# SchematicEasyEDA.net
KiCad netlist of a schematic drawn in EasyEDA
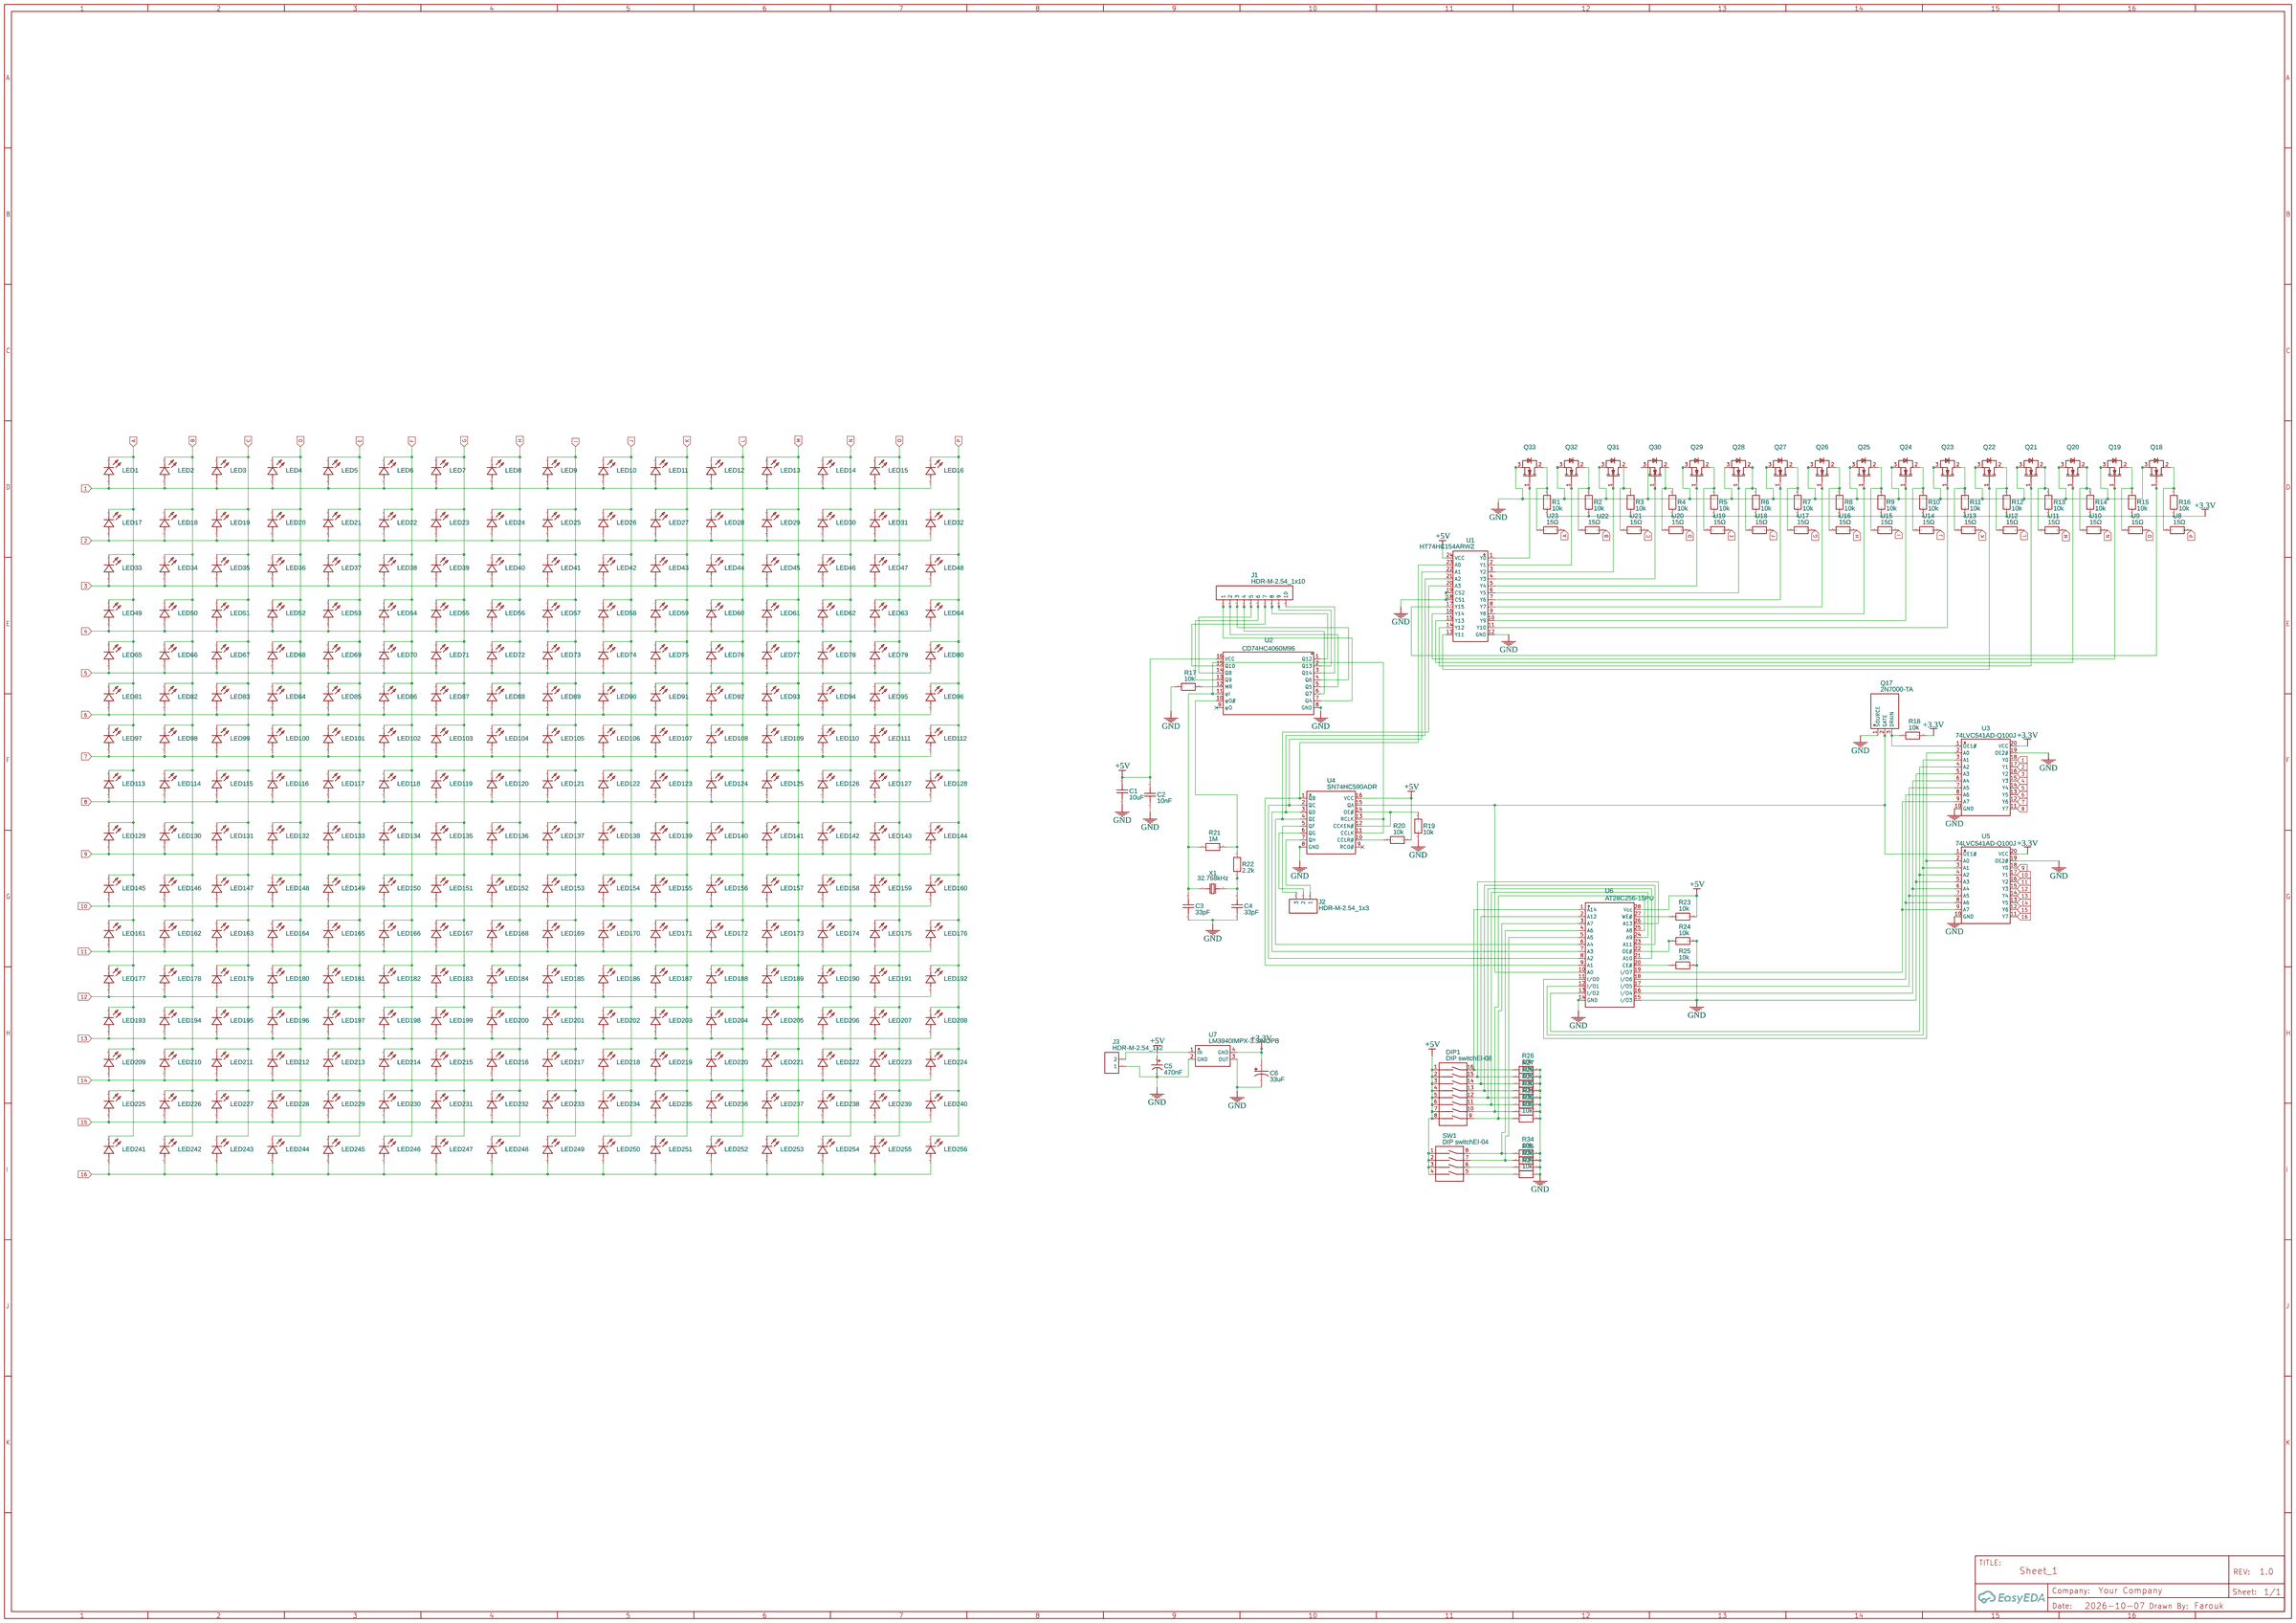
[diagram p0: schematic sheet]

(export (version "E")
  (design (tool "Eeschema 10.0.6"))
  (components
    (comp (ref "C1")
      (value "10uF")
      (fields
        (field (name "Manufacturer Part") "CC1210Y5V16V106ZN")
        (field (name "Manufacturer") "TORCH(火炬)")
      )
      (libsource (lib "") (part "CC1210Y5V16V106ZN"))
    )
    (comp (ref "C2")
      (value "10nF")
      (fields
        (field (name "Manufacturer Part") "CSA0805C0G103J500MT")
        (field (name "Manufacturer") "HRE(芯声)")
      )
      (libsource (lib "") (part "CSA0805C0G103J500MT"))
    )
    (comp (ref "C3")
      (value "33pF")
      (fields (field (name "Manufacturer Part") "600F330JT250XT") (field (name "Manufacturer") "Kyocera AVX"))
      (libsource (lib "") (part "600F330JT250XT"))
    )
    (comp (ref "C4")
      (value "33pF")
      (fields (field (name "Manufacturer Part") "600F330JT250XT") (field (name "Manufacturer") "Kyocera AVX"))
      (libsource (lib "") (part "600F330JT250XT"))
    )
    (comp (ref "C5")
      (value "470nF")
      (fields
        (field (name "Manufacturer Part") "kF474M050C05RR0VH2FP0")
        (field (name "Manufacturer") "Chengx(承兴)")
      )
      (libsource (lib "") (part "0.47uF 50V 4*5"))
    )
    (comp (ref "C6")
      (value "33uF")
      (fields
        (field (name "Manufacturer Part") "ECR1HPT330MLL063011")
        (field (name "Manufacturer") "Jianghai(南通江海)")
      )
      (libsource (lib "") (part "ECR1HPT330MLL063011"))
    )
    (comp (ref "DIP1")
      (value "DIP switchEI-08")
      (fields (field (name "Manufacturer Part") "EI-08-V") (field (name "Manufacturer") "Diptronics(圜达)"))
      (libsource (lib "") (part "DIP switchEI-08"))
    )
    (comp (ref "J1")
      (value "HDR-M-2.54_1x10")
      (fields
        (field (name "Manufacturer Part") "HX PZ-2005WV-1x10P")
        (field (name "Manufacturer") "hanxia(韩下)")
      )
      (libsource (lib "") (part "HDR-M-2.54_1x10"))
    )
    (comp (ref "J2")
      (value "HDR-M-2.54_1x3")
      (fields
        (field (name "Manufacturer Part") "5557WRF-1X3P(HDGC4201WR-F-1X3P)")
        (field (name "Manufacturer") "HDGC(华德共创)")
      )
      (libsource (lib "") (part "HDR-M-2.54_1x3"))
    )
    (comp (ref "J3") (value "HDR-M-2.54_1x2") (libsource (lib "") (part "HDR-M-2.54_1x2")))
    (comp (ref "LED1")
      (value "42-21A/GHC-YX1Y2N/1T")
      (fields (field (name "Manufacturer") "EVERLIGHT(亿光)"))
      (libsource (lib "") (part "42-21A/GHC-YX1Y2N/1T"))
    )
    (comp (ref "LED2")
      (value "42-21A/GHC-YX1Y2N/1T")
      (fields (field (name "Manufacturer") "EVERLIGHT(亿光)"))
      (libsource (lib "") (part "42-21A/GHC-YX1Y2N/1T"))
    )
    (comp (ref "LED3")
      (value "42-21A/GHC-YX1Y2N/1T")
      (fields (field (name "Manufacturer") "EVERLIGHT(亿光)"))
      (libsource (lib "") (part "42-21A/GHC-YX1Y2N/1T"))
    )
    (comp (ref "LED4")
      (value "42-21A/GHC-YX1Y2N/1T")
      (fields (field (name "Manufacturer") "EVERLIGHT(亿光)"))
      (libsource (lib "") (part "42-21A/GHC-YX1Y2N/1T"))
    )
    (comp (ref "LED5")
      (value "42-21A/GHC-YX1Y2N/1T")
      (fields (field (name "Manufacturer") "EVERLIGHT(亿光)"))
      (libsource (lib "") (part "42-21A/GHC-YX1Y2N/1T"))
    )
    (comp (ref "LED6")
      (value "42-21A/GHC-YX1Y2N/1T")
      (fields (field (name "Manufacturer") "EVERLIGHT(亿光)"))
      (libsource (lib "") (part "42-21A/GHC-YX1Y2N/1T"))
    )
    (comp (ref "LED7")
      (value "42-21A/GHC-YX1Y2N/1T")
      (fields (field (name "Manufacturer") "EVERLIGHT(亿光)"))
      (libsource (lib "") (part "42-21A/GHC-YX1Y2N/1T"))
    )
    (comp (ref "LED8")
      (value "42-21A/GHC-YX1Y2N/1T")
      (fields (field (name "Manufacturer") "EVERLIGHT(亿光)"))
      (libsource (lib "") (part "42-21A/GHC-YX1Y2N/1T"))
    )
    (comp (ref "LED9")
      (value "42-21A/GHC-YX1Y2N/1T")
      (fields (field (name "Manufacturer") "EVERLIGHT(亿光)"))
      (libsource (lib "") (part "42-21A/GHC-YX1Y2N/1T"))
    )
    (comp (ref "LED10")
      (value "42-21A/GHC-YX1Y2N/1T")
      (fields (field (name "Manufacturer") "EVERLIGHT(亿光)"))
      (libsource (lib "") (part "42-21A/GHC-YX1Y2N/1T"))
    )
    (comp (ref "LED11")
      (value "42-21A/GHC-YX1Y2N/1T")
      (fields (field (name "Manufacturer") "EVERLIGHT(亿光)"))
      (libsource (lib "") (part "42-21A/GHC-YX1Y2N/1T"))
    )
    (comp (ref "LED12")
      (value "42-21A/GHC-YX1Y2N/1T")
      (fields (field (name "Manufacturer") "EVERLIGHT(亿光)"))
      (libsource (lib "") (part "42-21A/GHC-YX1Y2N/1T"))
    )
    (comp (ref "LED13")
      (value "42-21A/GHC-YX1Y2N/1T")
      (fields (field (name "Manufacturer") "EVERLIGHT(亿光)"))
      (libsource (lib "") (part "42-21A/GHC-YX1Y2N/1T"))
    )
    (comp (ref "LED14")
      (value "42-21A/GHC-YX1Y2N/1T")
      (fields (field (name "Manufacturer") "EVERLIGHT(亿光)"))
      (libsource (lib "") (part "42-21A/GHC-YX1Y2N/1T"))
    )
    (comp (ref "LED15")
      (value "42-21A/GHC-YX1Y2N/1T")
      (fields (field (name "Manufacturer") "EVERLIGHT(亿光)"))
      (libsource (lib "") (part "42-21A/GHC-YX1Y2N/1T"))
    )
    (comp (ref "LED16")
      (value "42-21A/GHC-YX1Y2N/1T")
      (fields (field (name "Manufacturer") "EVERLIGHT(亿光)"))
      (libsource (lib "") (part "42-21A/GHC-YX1Y2N/1T"))
    )
    (comp (ref "LED17")
      (value "42-21A/GHC-YX1Y2N/1T")
      (fields (field (name "Manufacturer") "EVERLIGHT(亿光)"))
      (libsource (lib "") (part "42-21A/GHC-YX1Y2N/1T"))
    )
    (comp (ref "LED18")
      (value "42-21A/GHC-YX1Y2N/1T")
      (fields (field (name "Manufacturer") "EVERLIGHT(亿光)"))
      (libsource (lib "") (part "42-21A/GHC-YX1Y2N/1T"))
    )
    (comp (ref "LED19")
      (value "42-21A/GHC-YX1Y2N/1T")
      (fields (field (name "Manufacturer") "EVERLIGHT(亿光)"))
      (libsource (lib "") (part "42-21A/GHC-YX1Y2N/1T"))
    )
    (comp (ref "LED20")
      (value "42-21A/GHC-YX1Y2N/1T")
      (fields (field (name "Manufacturer") "EVERLIGHT(亿光)"))
      (libsource (lib "") (part "42-21A/GHC-YX1Y2N/1T"))
    )
    (comp (ref "LED21")
      (value "42-21A/GHC-YX1Y2N/1T")
      (fields (field (name "Manufacturer") "EVERLIGHT(亿光)"))
      (libsource (lib "") (part "42-21A/GHC-YX1Y2N/1T"))
    )
    (comp (ref "LED22")
      (value "42-21A/GHC-YX1Y2N/1T")
      (fields (field (name "Manufacturer") "EVERLIGHT(亿光)"))
      (libsource (lib "") (part "42-21A/GHC-YX1Y2N/1T"))
    )
    (comp (ref "LED23")
      (value "42-21A/GHC-YX1Y2N/1T")
      (fields (field (name "Manufacturer") "EVERLIGHT(亿光)"))
      (libsource (lib "") (part "42-21A/GHC-YX1Y2N/1T"))
    )
    (comp (ref "LED24")
      (value "42-21A/GHC-YX1Y2N/1T")
      (fields (field (name "Manufacturer") "EVERLIGHT(亿光)"))
      (libsource (lib "") (part "42-21A/GHC-YX1Y2N/1T"))
    )
    (comp (ref "LED25")
      (value "42-21A/GHC-YX1Y2N/1T")
      (fields (field (name "Manufacturer") "EVERLIGHT(亿光)"))
      (libsource (lib "") (part "42-21A/GHC-YX1Y2N/1T"))
    )
    (comp (ref "LED26")
      (value "42-21A/GHC-YX1Y2N/1T")
      (fields (field (name "Manufacturer") "EVERLIGHT(亿光)"))
      (libsource (lib "") (part "42-21A/GHC-YX1Y2N/1T"))
    )
    (comp (ref "LED27")
      (value "42-21A/GHC-YX1Y2N/1T")
      (fields (field (name "Manufacturer") "EVERLIGHT(亿光)"))
      (libsource (lib "") (part "42-21A/GHC-YX1Y2N/1T"))
    )
    (comp (ref "LED28")
      (value "42-21A/GHC-YX1Y2N/1T")
      (fields (field (name "Manufacturer") "EVERLIGHT(亿光)"))
      (libsource (lib "") (part "42-21A/GHC-YX1Y2N/1T"))
    )
    (comp (ref "LED29")
      (value "42-21A/GHC-YX1Y2N/1T")
      (fields (field (name "Manufacturer") "EVERLIGHT(亿光)"))
      (libsource (lib "") (part "42-21A/GHC-YX1Y2N/1T"))
    )
    (comp (ref "LED30")
      (value "42-21A/GHC-YX1Y2N/1T")
      (fields (field (name "Manufacturer") "EVERLIGHT(亿光)"))
      (libsource (lib "") (part "42-21A/GHC-YX1Y2N/1T"))
    )
    (comp (ref "LED31")
      (value "42-21A/GHC-YX1Y2N/1T")
      (fields (field (name "Manufacturer") "EVERLIGHT(亿光)"))
      (libsource (lib "") (part "42-21A/GHC-YX1Y2N/1T"))
    )
    (comp (ref "LED32")
      (value "42-21A/GHC-YX1Y2N/1T")
      (fields (field (name "Manufacturer") "EVERLIGHT(亿光)"))
      (libsource (lib "") (part "42-21A/GHC-YX1Y2N/1T"))
    )
    (comp (ref "LED33")
      (value "42-21A/GHC-YX1Y2N/1T")
      (fields (field (name "Manufacturer") "EVERLIGHT(亿光)"))
      (libsource (lib "") (part "42-21A/GHC-YX1Y2N/1T"))
    )
    (comp (ref "LED34")
      (value "42-21A/GHC-YX1Y2N/1T")
      (fields (field (name "Manufacturer") "EVERLIGHT(亿光)"))
      (libsource (lib "") (part "42-21A/GHC-YX1Y2N/1T"))
    )
    (comp (ref "LED35")
      (value "42-21A/GHC-YX1Y2N/1T")
      (fields (field (name "Manufacturer") "EVERLIGHT(亿光)"))
      (libsource (lib "") (part "42-21A/GHC-YX1Y2N/1T"))
    )
    (comp (ref "LED36")
      (value "42-21A/GHC-YX1Y2N/1T")
      (fields (field (name "Manufacturer") "EVERLIGHT(亿光)"))
      (libsource (lib "") (part "42-21A/GHC-YX1Y2N/1T"))
    )
    (comp (ref "LED37")
      (value "42-21A/GHC-YX1Y2N/1T")
      (fields (field (name "Manufacturer") "EVERLIGHT(亿光)"))
      (libsource (lib "") (part "42-21A/GHC-YX1Y2N/1T"))
    )
    (comp (ref "LED38")
      (value "42-21A/GHC-YX1Y2N/1T")
      (fields (field (name "Manufacturer") "EVERLIGHT(亿光)"))
      (libsource (lib "") (part "42-21A/GHC-YX1Y2N/1T"))
    )
    (comp (ref "LED39")
      (value "42-21A/GHC-YX1Y2N/1T")
      (fields (field (name "Manufacturer") "EVERLIGHT(亿光)"))
      (libsource (lib "") (part "42-21A/GHC-YX1Y2N/1T"))
    )
    (comp (ref "LED40")
      (value "42-21A/GHC-YX1Y2N/1T")
      (fields (field (name "Manufacturer") "EVERLIGHT(亿光)"))
      (libsource (lib "") (part "42-21A/GHC-YX1Y2N/1T"))
    )
    (comp (ref "LED41")
      (value "42-21A/GHC-YX1Y2N/1T")
      (fields (field (name "Manufacturer") "EVERLIGHT(亿光)"))
      (libsource (lib "") (part "42-21A/GHC-YX1Y2N/1T"))
    )
    (comp (ref "LED42")
      (value "42-21A/GHC-YX1Y2N/1T")
      (fields (field (name "Manufacturer") "EVERLIGHT(亿光)"))
      (libsource (lib "") (part "42-21A/GHC-YX1Y2N/1T"))
    )
    (comp (ref "LED43")
      (value "42-21A/GHC-YX1Y2N/1T")
      (fields (field (name "Manufacturer") "EVERLIGHT(亿光)"))
      (libsource (lib "") (part "42-21A/GHC-YX1Y2N/1T"))
    )
    (comp (ref "LED44")
      (value "42-21A/GHC-YX1Y2N/1T")
      (fields (field (name "Manufacturer") "EVERLIGHT(亿光)"))
      (libsource (lib "") (part "42-21A/GHC-YX1Y2N/1T"))
    )
    (comp (ref "LED45")
      (value "42-21A/GHC-YX1Y2N/1T")
      (fields (field (name "Manufacturer") "EVERLIGHT(亿光)"))
      (libsource (lib "") (part "42-21A/GHC-YX1Y2N/1T"))
    )
    (comp (ref "LED46")
      (value "42-21A/GHC-YX1Y2N/1T")
      (fields (field (name "Manufacturer") "EVERLIGHT(亿光)"))
      (libsource (lib "") (part "42-21A/GHC-YX1Y2N/1T"))
    )
    (comp (ref "LED47")
      (value "42-21A/GHC-YX1Y2N/1T")
      (fields (field (name "Manufacturer") "EVERLIGHT(亿光)"))
      (libsource (lib "") (part "42-21A/GHC-YX1Y2N/1T"))
    )
    (comp (ref "LED48")
      (value "42-21A/GHC-YX1Y2N/1T")
      (fields (field (name "Manufacturer") "EVERLIGHT(亿光)"))
      (libsource (lib "") (part "42-21A/GHC-YX1Y2N/1T"))
    )
    (comp (ref "LED49")
      (value "42-21A/GHC-YX1Y2N/1T")
      (fields (field (name "Manufacturer") "EVERLIGHT(亿光)"))
      (libsource (lib "") (part "42-21A/GHC-YX1Y2N/1T"))
    )
    (comp (ref "LED50")
      (value "42-21A/GHC-YX1Y2N/1T")
      (fields (field (name "Manufacturer") "EVERLIGHT(亿光)"))
      (libsource (lib "") (part "42-21A/GHC-YX1Y2N/1T"))
    )
    (comp (ref "LED51")
      (value "42-21A/GHC-YX1Y2N/1T")
      (fields (field (name "Manufacturer") "EVERLIGHT(亿光)"))
      (libsource (lib "") (part "42-21A/GHC-YX1Y2N/1T"))
    )
    (comp (ref "LED52")
      (value "42-21A/GHC-YX1Y2N/1T")
      (fields (field (name "Manufacturer") "EVERLIGHT(亿光)"))
      (libsource (lib "") (part "42-21A/GHC-YX1Y2N/1T"))
    )
    (comp (ref "LED53")
      (value "42-21A/GHC-YX1Y2N/1T")
      (fields (field (name "Manufacturer") "EVERLIGHT(亿光)"))
      (libsource (lib "") (part "42-21A/GHC-YX1Y2N/1T"))
    )
    (comp (ref "LED54")
      (value "42-21A/GHC-YX1Y2N/1T")
      (fields (field (name "Manufacturer") "EVERLIGHT(亿光)"))
      (libsource (lib "") (part "42-21A/GHC-YX1Y2N/1T"))
    )
    (comp (ref "LED55")
      (value "42-21A/GHC-YX1Y2N/1T")
      (fields (field (name "Manufacturer") "EVERLIGHT(亿光)"))
      (libsource (lib "") (part "42-21A/GHC-YX1Y2N/1T"))
    )
    (comp (ref "LED56")
      (value "42-21A/GHC-YX1Y2N/1T")
      (fields (field (name "Manufacturer") "EVERLIGHT(亿光)"))
      (libsource (lib "") (part "42-21A/GHC-YX1Y2N/1T"))
    )
    (comp (ref "LED57")
      (value "42-21A/GHC-YX1Y2N/1T")
      (fields (field (name "Manufacturer") "EVERLIGHT(亿光)"))
      (libsource (lib "") (part "42-21A/GHC-YX1Y2N/1T"))
    )
    (comp (ref "LED58")
      (value "42-21A/GHC-YX1Y2N/1T")
      (fields (field (name "Manufacturer") "EVERLIGHT(亿光)"))
      (libsource (lib "") (part "42-21A/GHC-YX1Y2N/1T"))
    )
    (comp (ref "LED59")
      (value "42-21A/GHC-YX1Y2N/1T")
      (fields (field (name "Manufacturer") "EVERLIGHT(亿光)"))
      (libsource (lib "") (part "42-21A/GHC-YX1Y2N/1T"))
    )
    (comp (ref "LED60")
      (value "42-21A/GHC-YX1Y2N/1T")
      (fields (field (name "Manufacturer") "EVERLIGHT(亿光)"))
      (libsource (lib "") (part "42-21A/GHC-YX1Y2N/1T"))
    )
    (comp (ref "LED61")
      (value "42-21A/GHC-YX1Y2N/1T")
      (fields (field (name "Manufacturer") "EVERLIGHT(亿光)"))
      (libsource (lib "") (part "42-21A/GHC-YX1Y2N/1T"))
    )
    (comp (ref "LED62")
      (value "42-21A/GHC-YX1Y2N/1T")
      (fields (field (name "Manufacturer") "EVERLIGHT(亿光)"))
      (libsource (lib "") (part "42-21A/GHC-YX1Y2N/1T"))
    )
    (comp (ref "LED63")
      (value "42-21A/GHC-YX1Y2N/1T")
      (fields (field (name "Manufacturer") "EVERLIGHT(亿光)"))
      (libsource (lib "") (part "42-21A/GHC-YX1Y2N/1T"))
    )
    (comp (ref "LED64")
      (value "42-21A/GHC-YX1Y2N/1T")
      (fields (field (name "Manufacturer") "EVERLIGHT(亿光)"))
      (libsource (lib "") (part "42-21A/GHC-YX1Y2N/1T"))
    )
    (comp (ref "LED65")
      (value "42-21A/GHC-YX1Y2N/1T")
      (fields (field (name "Manufacturer") "EVERLIGHT(亿光)"))
      (libsource (lib "") (part "42-21A/GHC-YX1Y2N/1T"))
    )
    (comp (ref "LED66")
      (value "42-21A/GHC-YX1Y2N/1T")
      (fields (field (name "Manufacturer") "EVERLIGHT(亿光)"))
      (libsource (lib "") (part "42-21A/GHC-YX1Y2N/1T"))
    )
    (comp (ref "LED67")
      (value "42-21A/GHC-YX1Y2N/1T")
      (fields (field (name "Manufacturer") "EVERLIGHT(亿光)"))
      (libsource (lib "") (part "42-21A/GHC-YX1Y2N/1T"))
    )
    (comp (ref "LED68")
      (value "42-21A/GHC-YX1Y2N/1T")
      (fields (field (name "Manufacturer") "EVERLIGHT(亿光)"))
      (libsource (lib "") (part "42-21A/GHC-YX1Y2N/1T"))
    )
    (comp (ref "LED69")
      (value "42-21A/GHC-YX1Y2N/1T")
      (fields (field (name "Manufacturer") "EVERLIGHT(亿光)"))
      (libsource (lib "") (part "42-21A/GHC-YX1Y2N/1T"))
    )
    (comp (ref "LED70")
      (value "42-21A/GHC-YX1Y2N/1T")
      (fields (field (name "Manufacturer") "EVERLIGHT(亿光)"))
      (libsource (lib "") (part "42-21A/GHC-YX1Y2N/1T"))
    )
    (comp (ref "LED71")
      (value "42-21A/GHC-YX1Y2N/1T")
      (fields (field (name "Manufacturer") "EVERLIGHT(亿光)"))
      (libsource (lib "") (part "42-21A/GHC-YX1Y2N/1T"))
    )
    (comp (ref "LED72")
      (value "42-21A/GHC-YX1Y2N/1T")
      (fields (field (name "Manufacturer") "EVERLIGHT(亿光)"))
      (libsource (lib "") (part "42-21A/GHC-YX1Y2N/1T"))
    )
    (comp (ref "LED73")
      (value "42-21A/GHC-YX1Y2N/1T")
      (fields (field (name "Manufacturer") "EVERLIGHT(亿光)"))
      (libsource (lib "") (part "42-21A/GHC-YX1Y2N/1T"))
    )
    (comp (ref "LED74")
      (value "42-21A/GHC-YX1Y2N/1T")
      (fields (field (name "Manufacturer") "EVERLIGHT(亿光)"))
      (libsource (lib "") (part "42-21A/GHC-YX1Y2N/1T"))
    )
    (comp (ref "LED75")
      (value "42-21A/GHC-YX1Y2N/1T")
      (fields (field (name "Manufacturer") "EVERLIGHT(亿光)"))
      (libsource (lib "") (part "42-21A/GHC-YX1Y2N/1T"))
    )
    (comp (ref "LED76")
      (value "42-21A/GHC-YX1Y2N/1T")
      (fields (field (name "Manufacturer") "EVERLIGHT(亿光)"))
      (libsource (lib "") (part "42-21A/GHC-YX1Y2N/1T"))
    )
    (comp (ref "LED77")
      (value "42-21A/GHC-YX1Y2N/1T")
      (fields (field (name "Manufacturer") "EVERLIGHT(亿光)"))
      (libsource (lib "") (part "42-21A/GHC-YX1Y2N/1T"))
    )
    (comp (ref "LED78")
      (value "42-21A/GHC-YX1Y2N/1T")
      (fields (field (name "Manufacturer") "EVERLIGHT(亿光)"))
      (libsource (lib "") (part "42-21A/GHC-YX1Y2N/1T"))
    )
    (comp (ref "LED79")
      (value "42-21A/GHC-YX1Y2N/1T")
      (fields (field (name "Manufacturer") "EVERLIGHT(亿光)"))
      (libsource (lib "") (part "42-21A/GHC-YX1Y2N/1T"))
    )
    (comp (ref "LED80")
      (value "42-21A/GHC-YX1Y2N/1T")
      (fields (field (name "Manufacturer") "EVERLIGHT(亿光)"))
      (libsource (lib "") (part "42-21A/GHC-YX1Y2N/1T"))
    )
    (comp (ref "LED81")
      (value "42-21A/GHC-YX1Y2N/1T")
      (fields (field (name "Manufacturer") "EVERLIGHT(亿光)"))
      (libsource (lib "") (part "42-21A/GHC-YX1Y2N/1T"))
    )
    (comp (ref "LED82")
      (value "42-21A/GHC-YX1Y2N/1T")
      (fields (field (name "Manufacturer") "EVERLIGHT(亿光)"))
      (libsource (lib "") (part "42-21A/GHC-YX1Y2N/1T"))
    )
    (comp (ref "LED83")
      (value "42-21A/GHC-YX1Y2N/1T")
      (fields (field (name "Manufacturer") "EVERLIGHT(亿光)"))
      (libsource (lib "") (part "42-21A/GHC-YX1Y2N/1T"))
    )
    (comp (ref "LED84")
      (value "42-21A/GHC-YX1Y2N/1T")
      (fields (field (name "Manufacturer") "EVERLIGHT(亿光)"))
      (libsource (lib "") (part "42-21A/GHC-YX1Y2N/1T"))
    )
    (comp (ref "LED85")
      (value "42-21A/GHC-YX1Y2N/1T")
      (fields (field (name "Manufacturer") "EVERLIGHT(亿光)"))
      (libsource (lib "") (part "42-21A/GHC-YX1Y2N/1T"))
    )
    (comp (ref "LED86")
      (value "42-21A/GHC-YX1Y2N/1T")
      (fields (field (name "Manufacturer") "EVERLIGHT(亿光)"))
      (libsource (lib "") (part "42-21A/GHC-YX1Y2N/1T"))
    )
    (comp (ref "LED87")
      (value "42-21A/GHC-YX1Y2N/1T")
      (fields (field (name "Manufacturer") "EVERLIGHT(亿光)"))
      (libsource (lib "") (part "42-21A/GHC-YX1Y2N/1T"))
    )
    (comp (ref "LED88")
      (value "42-21A/GHC-YX1Y2N/1T")
      (fields (field (name "Manufacturer") "EVERLIGHT(亿光)"))
      (libsource (lib "") (part "42-21A/GHC-YX1Y2N/1T"))
    )
    (comp (ref "LED89")
      (value "42-21A/GHC-YX1Y2N/1T")
      (fields (field (name "Manufacturer") "EVERLIGHT(亿光)"))
      (libsource (lib "") (part "42-21A/GHC-YX1Y2N/1T"))
    )
    (comp (ref "LED90")
      (value "42-21A/GHC-YX1Y2N/1T")
      (fields (field (name "Manufacturer") "EVERLIGHT(亿光)"))
      (libsource (lib "") (part "42-21A/GHC-YX1Y2N/1T"))
    )
    (comp (ref "LED91")
      (value "42-21A/GHC-YX1Y2N/1T")
      (fields (field (name "Manufacturer") "EVERLIGHT(亿光)"))
      (libsource (lib "") (part "42-21A/GHC-YX1Y2N/1T"))
    )
    (comp (ref "LED92")
      (value "42-21A/GHC-YX1Y2N/1T")
      (fields (field (name "Manufacturer") "EVERLIGHT(亿光)"))
      (libsource (lib "") (part "42-21A/GHC-YX1Y2N/1T"))
    )
    (comp (ref "LED93")
      (value "42-21A/GHC-YX1Y2N/1T")
      (fields (field (name "Manufacturer") "EVERLIGHT(亿光)"))
      (libsource (lib "") (part "42-21A/GHC-YX1Y2N/1T"))
    )
    (comp (ref "LED94")
      (value "42-21A/GHC-YX1Y2N/1T")
      (fields (field (name "Manufacturer") "EVERLIGHT(亿光)"))
      (libsource (lib "") (part "42-21A/GHC-YX1Y2N/1T"))
    )
    (comp (ref "LED95")
      (value "42-21A/GHC-YX1Y2N/1T")
      (fields (field (name "Manufacturer") "EVERLIGHT(亿光)"))
      (libsource (lib "") (part "42-21A/GHC-YX1Y2N/1T"))
    )
    (comp (ref "LED96")
      (value "42-21A/GHC-YX1Y2N/1T")
      (fields (field (name "Manufacturer") "EVERLIGHT(亿光)"))
      (libsource (lib "") (part "42-21A/GHC-YX1Y2N/1T"))
    )
    (comp (ref "LED97")
      (value "42-21A/GHC-YX1Y2N/1T")
      (fields (field (name "Manufacturer") "EVERLIGHT(亿光)"))
      (libsource (lib "") (part "42-21A/GHC-YX1Y2N/1T"))
    )
    (comp (ref "LED98")
      (value "42-21A/GHC-YX1Y2N/1T")
      (fields (field (name "Manufacturer") "EVERLIGHT(亿光)"))
      (libsource (lib "") (part "42-21A/GHC-YX1Y2N/1T"))
    )
    (comp (ref "LED99")
      (value "42-21A/GHC-YX1Y2N/1T")
      (fields (field (name "Manufacturer") "EVERLIGHT(亿光)"))
      (libsource (lib "") (part "42-21A/GHC-YX1Y2N/1T"))
    )
    (comp (ref "LED100")
      (value "42-21A/GHC-YX1Y2N/1T")
      (fields (field (name "Manufacturer") "EVERLIGHT(亿光)"))
      (libsource (lib "") (part "42-21A/GHC-YX1Y2N/1T"))
    )
    (comp (ref "LED101")
      (value "42-21A/GHC-YX1Y2N/1T")
      (fields (field (name "Manufacturer") "EVERLIGHT(亿光)"))
      (libsource (lib "") (part "42-21A/GHC-YX1Y2N/1T"))
    )
    (comp (ref "LED102")
      (value "42-21A/GHC-YX1Y2N/1T")
      (fields (field (name "Manufacturer") "EVERLIGHT(亿光)"))
      (libsource (lib "") (part "42-21A/GHC-YX1Y2N/1T"))
    )
    (comp (ref "LED103")
      (value "42-21A/GHC-YX1Y2N/1T")
      (fields (field (name "Manufacturer") "EVERLIGHT(亿光)"))
      (libsource (lib "") (part "42-21A/GHC-YX1Y2N/1T"))
    )
    (comp (ref "LED104")
      (value "42-21A/GHC-YX1Y2N/1T")
      (fields (field (name "Manufacturer") "EVERLIGHT(亿光)"))
      (libsource (lib "") (part "42-21A/GHC-YX1Y2N/1T"))
    )
    (comp (ref "LED105")
      (value "42-21A/GHC-YX1Y2N/1T")
      (fields (field (name "Manufacturer") "EVERLIGHT(亿光)"))
      (libsource (lib "") (part "42-21A/GHC-YX1Y2N/1T"))
    )
    (comp (ref "LED106")
      (value "42-21A/GHC-YX1Y2N/1T")
      (fields (field (name "Manufacturer") "EVERLIGHT(亿光)"))
      (libsource (lib "") (part "42-21A/GHC-YX1Y2N/1T"))
    )
    (comp (ref "LED107")
      (value "42-21A/GHC-YX1Y2N/1T")
      (fields (field (name "Manufacturer") "EVERLIGHT(亿光)"))
      (libsource (lib "") (part "42-21A/GHC-YX1Y2N/1T"))
    )
    (comp (ref "LED108")
      (value "42-21A/GHC-YX1Y2N/1T")
      (fields (field (name "Manufacturer") "EVERLIGHT(亿光)"))
      (libsource (lib "") (part "42-21A/GHC-YX1Y2N/1T"))
    )
    (comp (ref "LED109")
      (value "42-21A/GHC-YX1Y2N/1T")
      (fields (field (name "Manufacturer") "EVERLIGHT(亿光)"))
      (libsource (lib "") (part "42-21A/GHC-YX1Y2N/1T"))
    )
    (comp (ref "LED110")
      (value "42-21A/GHC-YX1Y2N/1T")
      (fields (field (name "Manufacturer") "EVERLIGHT(亿光)"))
      (libsource (lib "") (part "42-21A/GHC-YX1Y2N/1T"))
    )
    (comp (ref "LED111")
      (value "42-21A/GHC-YX1Y2N/1T")
      (fields (field (name "Manufacturer") "EVERLIGHT(亿光)"))
      (libsource (lib "") (part "42-21A/GHC-YX1Y2N/1T"))
    )
    (comp (ref "LED112")
      (value "42-21A/GHC-YX1Y2N/1T")
      (fields (field (name "Manufacturer") "EVERLIGHT(亿光)"))
      (libsource (lib "") (part "42-21A/GHC-YX1Y2N/1T"))
    )
    (comp (ref "LED113")
      (value "42-21A/GHC-YX1Y2N/1T")
      (fields (field (name "Manufacturer") "EVERLIGHT(亿光)"))
      (libsource (lib "") (part "42-21A/GHC-YX1Y2N/1T"))
    )
    (comp (ref "LED114")
      (value "42-21A/GHC-YX1Y2N/1T")
      (fields (field (name "Manufacturer") "EVERLIGHT(亿光)"))
      (libsource (lib "") (part "42-21A/GHC-YX1Y2N/1T"))
    )
    (comp (ref "LED115")
      (value "42-21A/GHC-YX1Y2N/1T")
      (fields (field (name "Manufacturer") "EVERLIGHT(亿光)"))
      (libsource (lib "") (part "42-21A/GHC-YX1Y2N/1T"))
    )
    (comp (ref "LED116")
      (value "42-21A/GHC-YX1Y2N/1T")
      (fields (field (name "Manufacturer") "EVERLIGHT(亿光)"))
      (libsource (lib "") (part "42-21A/GHC-YX1Y2N/1T"))
    )
    (comp (ref "LED117")
      (value "42-21A/GHC-YX1Y2N/1T")
      (fields (field (name "Manufacturer") "EVERLIGHT(亿光)"))
      (libsource (lib "") (part "42-21A/GHC-YX1Y2N/1T"))
    )
    (comp (ref "LED118")
      (value "42-21A/GHC-YX1Y2N/1T")
      (fields (field (name "Manufacturer") "EVERLIGHT(亿光)"))
      (libsource (lib "") (part "42-21A/GHC-YX1Y2N/1T"))
    )
    (comp (ref "LED119")
      (value "42-21A/GHC-YX1Y2N/1T")
      (fields (field (name "Manufacturer") "EVERLIGHT(亿光)"))
      (libsource (lib "") (part "42-21A/GHC-YX1Y2N/1T"))
    )
    (comp (ref "LED120")
      (value "42-21A/GHC-YX1Y2N/1T")
      (fields (field (name "Manufacturer") "EVERLIGHT(亿光)"))
      (libsource (lib "") (part "42-21A/GHC-YX1Y2N/1T"))
    )
    (comp (ref "LED121")
      (value "42-21A/GHC-YX1Y2N/1T")
      (fields (field (name "Manufacturer") "EVERLIGHT(亿光)"))
      (libsource (lib "") (part "42-21A/GHC-YX1Y2N/1T"))
    )
    (comp (ref "LED122")
      (value "42-21A/GHC-YX1Y2N/1T")
      (fields (field (name "Manufacturer") "EVERLIGHT(亿光)"))
      (libsource (lib "") (part "42-21A/GHC-YX1Y2N/1T"))
    )
    (comp (ref "LED123")
      (value "42-21A/GHC-YX1Y2N/1T")
      (fields (field (name "Manufacturer") "EVERLIGHT(亿光)"))
      (libsource (lib "") (part "42-21A/GHC-YX1Y2N/1T"))
    )
    (comp (ref "LED124")
      (value "42-21A/GHC-YX1Y2N/1T")
      (fields (field (name "Manufacturer") "EVERLIGHT(亿光)"))
      (libsource (lib "") (part "42-21A/GHC-YX1Y2N/1T"))
    )
    (comp (ref "LED125")
      (value "42-21A/GHC-YX1Y2N/1T")
      (fields (field (name "Manufacturer") "EVERLIGHT(亿光)"))
      (libsource (lib "") (part "42-21A/GHC-YX1Y2N/1T"))
    )
    (comp (ref "LED126")
      (value "42-21A/GHC-YX1Y2N/1T")
      (fields (field (name "Manufacturer") "EVERLIGHT(亿光)"))
      (libsource (lib "") (part "42-21A/GHC-YX1Y2N/1T"))
    )
    (comp (ref "LED127")
      (value "42-21A/GHC-YX1Y2N/1T")
      (fields (field (name "Manufacturer") "EVERLIGHT(亿光)"))
      (libsource (lib "") (part "42-21A/GHC-YX1Y2N/1T"))
    )
    (comp (ref "LED128")
      (value "42-21A/GHC-YX1Y2N/1T")
      (fields (field (name "Manufacturer") "EVERLIGHT(亿光)"))
      (libsource (lib "") (part "42-21A/GHC-YX1Y2N/1T"))
    )
    (comp (ref "LED129")
      (value "42-21A/GHC-YX1Y2N/1T")
      (fields (field (name "Manufacturer") "EVERLIGHT(亿光)"))
      (libsource (lib "") (part "42-21A/GHC-YX1Y2N/1T"))
    )
    (comp (ref "LED130")
      (value "42-21A/GHC-YX1Y2N/1T")
      (fields (field (name "Manufacturer") "EVERLIGHT(亿光)"))
      (libsource (lib "") (part "42-21A/GHC-YX1Y2N/1T"))
    )
    (comp (ref "LED131")
      (value "42-21A/GHC-YX1Y2N/1T")
      (fields (field (name "Manufacturer") "EVERLIGHT(亿光)"))
      (libsource (lib "") (part "42-21A/GHC-YX1Y2N/1T"))
    )
    (comp (ref "LED132")
      (value "42-21A/GHC-YX1Y2N/1T")
      (fields (field (name "Manufacturer") "EVERLIGHT(亿光)"))
      (libsource (lib "") (part "42-21A/GHC-YX1Y2N/1T"))
    )
    (comp (ref "LED133")
      (value "42-21A/GHC-YX1Y2N/1T")
      (fields (field (name "Manufacturer") "EVERLIGHT(亿光)"))
      (libsource (lib "") (part "42-21A/GHC-YX1Y2N/1T"))
    )
    (comp (ref "LED134")
      (value "42-21A/GHC-YX1Y2N/1T")
      (fields (field (name "Manufacturer") "EVERLIGHT(亿光)"))
      (libsource (lib "") (part "42-21A/GHC-YX1Y2N/1T"))
    )
    (comp (ref "LED135")
      (value "42-21A/GHC-YX1Y2N/1T")
      (fields (field (name "Manufacturer") "EVERLIGHT(亿光)"))
      (libsource (lib "") (part "42-21A/GHC-YX1Y2N/1T"))
    )
    (comp (ref "LED136")
      (value "42-21A/GHC-YX1Y2N/1T")
      (fields (field (name "Manufacturer") "EVERLIGHT(亿光)"))
      (libsource (lib "") (part "42-21A/GHC-YX1Y2N/1T"))
    )
    (comp (ref "LED137")
      (value "42-21A/GHC-YX1Y2N/1T")
      (fields (field (name "Manufacturer") "EVERLIGHT(亿光)"))
      (libsource (lib "") (part "42-21A/GHC-YX1Y2N/1T"))
    )
    (comp (ref "LED138")
      (value "42-21A/GHC-YX1Y2N/1T")
      (fields (field (name "Manufacturer") "EVERLIGHT(亿光)"))
      (libsource (lib "") (part "42-21A/GHC-YX1Y2N/1T"))
    )
    (comp (ref "LED139")
      (value "42-21A/GHC-YX1Y2N/1T")
      (fields (field (name "Manufacturer") "EVERLIGHT(亿光)"))
      (libsource (lib "") (part "42-21A/GHC-YX1Y2N/1T"))
    )
    (comp (ref "LED140")
      (value "42-21A/GHC-YX1Y2N/1T")
      (fields (field (name "Manufacturer") "EVERLIGHT(亿光)"))
      (libsource (lib "") (part "42-21A/GHC-YX1Y2N/1T"))
    )
    (comp (ref "LED141")
      (value "42-21A/GHC-YX1Y2N/1T")
      (fields (field (name "Manufacturer") "EVERLIGHT(亿光)"))
      (libsource (lib "") (part "42-21A/GHC-YX1Y2N/1T"))
    )
    (comp (ref "LED142")
      (value "42-21A/GHC-YX1Y2N/1T")
      (fields (field (name "Manufacturer") "EVERLIGHT(亿光)"))
      (libsource (lib "") (part "42-21A/GHC-YX1Y2N/1T"))
    )
    (comp (ref "LED143")
      (value "42-21A/GHC-YX1Y2N/1T")
      (fields (field (name "Manufacturer") "EVERLIGHT(亿光)"))
      (libsource (lib "") (part "42-21A/GHC-YX1Y2N/1T"))
    )
    (comp (ref "LED144")
      (value "42-21A/GHC-YX1Y2N/1T")
      (fields (field (name "Manufacturer") "EVERLIGHT(亿光)"))
      (libsource (lib "") (part "42-21A/GHC-YX1Y2N/1T"))
    )
    (comp (ref "LED145")
      (value "42-21A/GHC-YX1Y2N/1T")
      (fields (field (name "Manufacturer") "EVERLIGHT(亿光)"))
      (libsource (lib "") (part "42-21A/GHC-YX1Y2N/1T"))
    )
    (comp (ref "LED146")
      (value "42-21A/GHC-YX1Y2N/1T")
      (fields (field (name "Manufacturer") "EVERLIGHT(亿光)"))
      (libsource (lib "") (part "42-21A/GHC-YX1Y2N/1T"))
    )
    (comp (ref "LED147")
      (value "42-21A/GHC-YX1Y2N/1T")
      (fields (field (name "Manufacturer") "EVERLIGHT(亿光)"))
      (libsource (lib "") (part "42-21A/GHC-YX1Y2N/1T"))
    )
    (comp (ref "LED148")
      (value "42-21A/GHC-YX1Y2N/1T")
      (fields (field (name "Manufacturer") "EVERLIGHT(亿光)"))
      (libsource (lib "") (part "42-21A/GHC-YX1Y2N/1T"))
    )
    (comp (ref "LED149")
      (value "42-21A/GHC-YX1Y2N/1T")
      (fields (field (name "Manufacturer") "EVERLIGHT(亿光)"))
      (libsource (lib "") (part "42-21A/GHC-YX1Y2N/1T"))
    )
    (comp (ref "LED150")
      (value "42-21A/GHC-YX1Y2N/1T")
      (fields (field (name "Manufacturer") "EVERLIGHT(亿光)"))
      (libsource (lib "") (part "42-21A/GHC-YX1Y2N/1T"))
    )
    (comp (ref "LED151")
      (value "42-21A/GHC-YX1Y2N/1T")
      (fields (field (name "Manufacturer") "EVERLIGHT(亿光)"))
      (libsource (lib "") (part "42-21A/GHC-YX1Y2N/1T"))
    )
    (comp (ref "LED152")
      (value "42-21A/GHC-YX1Y2N/1T")
      (fields (field (name "Manufacturer") "EVERLIGHT(亿光)"))
      (libsource (lib "") (part "42-21A/GHC-YX1Y2N/1T"))
    )
    (comp (ref "LED153")
      (value "42-21A/GHC-YX1Y2N/1T")
      (fields (field (name "Manufacturer") "EVERLIGHT(亿光)"))
      (libsource (lib "") (part "42-21A/GHC-YX1Y2N/1T"))
    )
    (comp (ref "LED154")
      (value "42-21A/GHC-YX1Y2N/1T")
      (fields (field (name "Manufacturer") "EVERLIGHT(亿光)"))
      (libsource (lib "") (part "42-21A/GHC-YX1Y2N/1T"))
    )
    (comp (ref "LED155")
      (value "42-21A/GHC-YX1Y2N/1T")
      (fields (field (name "Manufacturer") "EVERLIGHT(亿光)"))
      (libsource (lib "") (part "42-21A/GHC-YX1Y2N/1T"))
    )
    (comp (ref "LED156")
      (value "42-21A/GHC-YX1Y2N/1T")
      (fields (field (name "Manufacturer") "EVERLIGHT(亿光)"))
      (libsource (lib "") (part "42-21A/GHC-YX1Y2N/1T"))
    )
    (comp (ref "LED157")
      (value "42-21A/GHC-YX1Y2N/1T")
      (fields (field (name "Manufacturer") "EVERLIGHT(亿光)"))
      (libsource (lib "") (part "42-21A/GHC-YX1Y2N/1T"))
    )
    (comp (ref "LED158")
      (value "42-21A/GHC-YX1Y2N/1T")
      (fields (field (name "Manufacturer") "EVERLIGHT(亿光)"))
      (libsource (lib "") (part "42-21A/GHC-YX1Y2N/1T"))
    )
    (comp (ref "LED159")
      (value "42-21A/GHC-YX1Y2N/1T")
      (fields (field (name "Manufacturer") "EVERLIGHT(亿光)"))
      (libsource (lib "") (part "42-21A/GHC-YX1Y2N/1T"))
    )
    (comp (ref "LED160")
      (value "42-21A/GHC-YX1Y2N/1T")
      (fields (field (name "Manufacturer") "EVERLIGHT(亿光)"))
      (libsource (lib "") (part "42-21A/GHC-YX1Y2N/1T"))
    )
    (comp (ref "LED161")
      (value "42-21A/GHC-YX1Y2N/1T")
      (fields (field (name "Manufacturer") "EVERLIGHT(亿光)"))
      (libsource (lib "") (part "42-21A/GHC-YX1Y2N/1T"))
    )
    (comp (ref "LED162")
      (value "42-21A/GHC-YX1Y2N/1T")
      (fields (field (name "Manufacturer") "EVERLIGHT(亿光)"))
      (libsource (lib "") (part "42-21A/GHC-YX1Y2N/1T"))
    )
    (comp (ref "LED163")
      (value "42-21A/GHC-YX1Y2N/1T")
      (fields (field (name "Manufacturer") "EVERLIGHT(亿光)"))
      (libsource (lib "") (part "42-21A/GHC-YX1Y2N/1T"))
    )
    (comp (ref "LED164")
      (value "42-21A/GHC-YX1Y2N/1T")
      (fields (field (name "Manufacturer") "EVERLIGHT(亿光)"))
      (libsource (lib "") (part "42-21A/GHC-YX1Y2N/1T"))
    )
    (comp (ref "LED165")
      (value "42-21A/GHC-YX1Y2N/1T")
      (fields (field (name "Manufacturer") "EVERLIGHT(亿光)"))
      (libsource (lib "") (part "42-21A/GHC-YX1Y2N/1T"))
    )
    (comp (ref "LED166")
      (value "42-21A/GHC-YX1Y2N/1T")
      (fields (field (name "Manufacturer") "EVERLIGHT(亿光)"))
      (libsource (lib "") (part "42-21A/GHC-YX1Y2N/1T"))
    )
    (comp (ref "LED167")
      (value "42-21A/GHC-YX1Y2N/1T")
      (fields (field (name "Manufacturer") "EVERLIGHT(亿光)"))
      (libsource (lib "") (part "42-21A/GHC-YX1Y2N/1T"))
    )
    (comp (ref "LED168")
      (value "42-21A/GHC-YX1Y2N/1T")
      (fields (field (name "Manufacturer") "EVERLIGHT(亿光)"))
      (libsource (lib "") (part "42-21A/GHC-YX1Y2N/1T"))
    )
    (comp (ref "LED169")
      (value "42-21A/GHC-YX1Y2N/1T")
      (fields (field (name "Manufacturer") "EVERLIGHT(亿光)"))
      (libsource (lib "") (part "42-21A/GHC-YX1Y2N/1T"))
    )
    (comp (ref "LED170")
      (value "42-21A/GHC-YX1Y2N/1T")
      (fields (field (name "Manufacturer") "EVERLIGHT(亿光)"))
      (libsource (lib "") (part "42-21A/GHC-YX1Y2N/1T"))
    )
    (comp (ref "LED171")
      (value "42-21A/GHC-YX1Y2N/1T")
      (fields (field (name "Manufacturer") "EVERLIGHT(亿光)"))
      (libsource (lib "") (part "42-21A/GHC-YX1Y2N/1T"))
    )
    (comp (ref "LED172")
      (value "42-21A/GHC-YX1Y2N/1T")
      (fields (field (name "Manufacturer") "EVERLIGHT(亿光)"))
      (libsource (lib "") (part "42-21A/GHC-YX1Y2N/1T"))
    )
    (comp (ref "LED173")
      (value "42-21A/GHC-YX1Y2N/1T")
      (fields (field (name "Manufacturer") "EVERLIGHT(亿光)"))
      (libsource (lib "") (part "42-21A/GHC-YX1Y2N/1T"))
    )
    (comp (ref "LED174")
      (value "42-21A/GHC-YX1Y2N/1T")
      (fields (field (name "Manufacturer") "EVERLIGHT(亿光)"))
      (libsource (lib "") (part "42-21A/GHC-YX1Y2N/1T"))
    )
    (comp (ref "LED175")
      (value "42-21A/GHC-YX1Y2N/1T")
      (fields (field (name "Manufacturer") "EVERLIGHT(亿光)"))
      (libsource (lib "") (part "42-21A/GHC-YX1Y2N/1T"))
    )
    (comp (ref "LED176")
      (value "42-21A/GHC-YX1Y2N/1T")
      (fields (field (name "Manufacturer") "EVERLIGHT(亿光)"))
      (libsource (lib "") (part "42-21A/GHC-YX1Y2N/1T"))
    )
    (comp (ref "LED177")
      (value "42-21A/GHC-YX1Y2N/1T")
      (fields (field (name "Manufacturer") "EVERLIGHT(亿光)"))
      (libsource (lib "") (part "42-21A/GHC-YX1Y2N/1T"))
    )
    (comp (ref "LED178")
      (value "42-21A/GHC-YX1Y2N/1T")
      (fields (field (name "Manufacturer") "EVERLIGHT(亿光)"))
      (libsource (lib "") (part "42-21A/GHC-YX1Y2N/1T"))
    )
    (comp (ref "LED179")
      (value "42-21A/GHC-YX1Y2N/1T")
      (fields (field (name "Manufacturer") "EVERLIGHT(亿光)"))
      (libsource (lib "") (part "42-21A/GHC-YX1Y2N/1T"))
    )
    (comp (ref "LED180")
      (value "42-21A/GHC-YX1Y2N/1T")
      (fields (field (name "Manufacturer") "EVERLIGHT(亿光)"))
      (libsource (lib "") (part "42-21A/GHC-YX1Y2N/1T"))
    )
    (comp (ref "LED181")
      (value "42-21A/GHC-YX1Y2N/1T")
      (fields (field (name "Manufacturer") "EVERLIGHT(亿光)"))
      (libsource (lib "") (part "42-21A/GHC-YX1Y2N/1T"))
    )
    (comp (ref "LED182")
      (value "42-21A/GHC-YX1Y2N/1T")
      (fields (field (name "Manufacturer") "EVERLIGHT(亿光)"))
      (libsource (lib "") (part "42-21A/GHC-YX1Y2N/1T"))
    )
    (comp (ref "LED183")
      (value "42-21A/GHC-YX1Y2N/1T")
      (fields (field (name "Manufacturer") "EVERLIGHT(亿光)"))
      (libsource (lib "") (part "42-21A/GHC-YX1Y2N/1T"))
    )
    (comp (ref "LED184")
      (value "42-21A/GHC-YX1Y2N/1T")
      (fields (field (name "Manufacturer") "EVERLIGHT(亿光)"))
      (libsource (lib "") (part "42-21A/GHC-YX1Y2N/1T"))
    )
    (comp (ref "LED185")
      (value "42-21A/GHC-YX1Y2N/1T")
      (fields (field (name "Manufacturer") "EVERLIGHT(亿光)"))
      (libsource (lib "") (part "42-21A/GHC-YX1Y2N/1T"))
    )
    (comp (ref "LED186")
      (value "42-21A/GHC-YX1Y2N/1T")
      (fields (field (name "Manufacturer") "EVERLIGHT(亿光)"))
      (libsource (lib "") (part "42-21A/GHC-YX1Y2N/1T"))
    )
    (comp (ref "LED187")
      (value "42-21A/GHC-YX1Y2N/1T")
      (fields (field (name "Manufacturer") "EVERLIGHT(亿光)"))
      (libsource (lib "") (part "42-21A/GHC-YX1Y2N/1T"))
    )
    (comp (ref "LED188")
      (value "42-21A/GHC-YX1Y2N/1T")
      (fields (field (name "Manufacturer") "EVERLIGHT(亿光)"))
      (libsource (lib "") (part "42-21A/GHC-YX1Y2N/1T"))
    )
    (comp (ref "LED189")
      (value "42-21A/GHC-YX1Y2N/1T")
      (fields (field (name "Manufacturer") "EVERLIGHT(亿光)"))
      (libsource (lib "") (part "42-21A/GHC-YX1Y2N/1T"))
    )
    (comp (ref "LED190")
      (value "42-21A/GHC-YX1Y2N/1T")
      (fields (field (name "Manufacturer") "EVERLIGHT(亿光)"))
      (libsource (lib "") (part "42-21A/GHC-YX1Y2N/1T"))
    )
    (comp (ref "LED191")
      (value "42-21A/GHC-YX1Y2N/1T")
      (fields (field (name "Manufacturer") "EVERLIGHT(亿光)"))
      (libsource (lib "") (part "42-21A/GHC-YX1Y2N/1T"))
    )
    (comp (ref "LED192")
      (value "42-21A/GHC-YX1Y2N/1T")
      (fields (field (name "Manufacturer") "EVERLIGHT(亿光)"))
      (libsource (lib "") (part "42-21A/GHC-YX1Y2N/1T"))
    )
    (comp (ref "LED193")
      (value "42-21A/GHC-YX1Y2N/1T")
      (fields (field (name "Manufacturer") "EVERLIGHT(亿光)"))
      (libsource (lib "") (part "42-21A/GHC-YX1Y2N/1T"))
    )
    (comp (ref "LED194")
      (value "42-21A/GHC-YX1Y2N/1T")
      (fields (field (name "Manufacturer") "EVERLIGHT(亿光)"))
      (libsource (lib "") (part "42-21A/GHC-YX1Y2N/1T"))
    )
    (comp (ref "LED195")
      (value "42-21A/GHC-YX1Y2N/1T")
      (fields (field (name "Manufacturer") "EVERLIGHT(亿光)"))
      (libsource (lib "") (part "42-21A/GHC-YX1Y2N/1T"))
    )
    (comp (ref "LED196")
      (value "42-21A/GHC-YX1Y2N/1T")
      (fields (field (name "Manufacturer") "EVERLIGHT(亿光)"))
      (libsource (lib "") (part "42-21A/GHC-YX1Y2N/1T"))
    )
    (comp (ref "LED197")
      (value "42-21A/GHC-YX1Y2N/1T")
      (fields (field (name "Manufacturer") "EVERLIGHT(亿光)"))
      (libsource (lib "") (part "42-21A/GHC-YX1Y2N/1T"))
    )
    (comp (ref "LED198")
      (value "42-21A/GHC-YX1Y2N/1T")
      (fields (field (name "Manufacturer") "EVERLIGHT(亿光)"))
      (libsource (lib "") (part "42-21A/GHC-YX1Y2N/1T"))
    )
    (comp (ref "LED199")
      (value "42-21A/GHC-YX1Y2N/1T")
      (fields (field (name "Manufacturer") "EVERLIGHT(亿光)"))
      (libsource (lib "") (part "42-21A/GHC-YX1Y2N/1T"))
    )
    (comp (ref "LED200")
      (value "42-21A/GHC-YX1Y2N/1T")
      (fields (field (name "Manufacturer") "EVERLIGHT(亿光)"))
      (libsource (lib "") (part "42-21A/GHC-YX1Y2N/1T"))
    )
    (comp (ref "LED201")
      (value "42-21A/GHC-YX1Y2N/1T")
      (fields (field (name "Manufacturer") "EVERLIGHT(亿光)"))
      (libsource (lib "") (part "42-21A/GHC-YX1Y2N/1T"))
    )
    (comp (ref "LED202")
      (value "42-21A/GHC-YX1Y2N/1T")
      (fields (field (name "Manufacturer") "EVERLIGHT(亿光)"))
      (libsource (lib "") (part "42-21A/GHC-YX1Y2N/1T"))
    )
    (comp (ref "LED203")
      (value "42-21A/GHC-YX1Y2N/1T")
      (fields (field (name "Manufacturer") "EVERLIGHT(亿光)"))
      (libsource (lib "") (part "42-21A/GHC-YX1Y2N/1T"))
    )
    (comp (ref "LED204")
      (value "42-21A/GHC-YX1Y2N/1T")
      (fields (field (name "Manufacturer") "EVERLIGHT(亿光)"))
      (libsource (lib "") (part "42-21A/GHC-YX1Y2N/1T"))
    )
    (comp (ref "LED205")
      (value "42-21A/GHC-YX1Y2N/1T")
      (fields (field (name "Manufacturer") "EVERLIGHT(亿光)"))
      (libsource (lib "") (part "42-21A/GHC-YX1Y2N/1T"))
    )
    (comp (ref "LED206")
      (value "42-21A/GHC-YX1Y2N/1T")
      (fields (field (name "Manufacturer") "EVERLIGHT(亿光)"))
      (libsource (lib "") (part "42-21A/GHC-YX1Y2N/1T"))
    )
    (comp (ref "LED207")
      (value "42-21A/GHC-YX1Y2N/1T")
      (fields (field (name "Manufacturer") "EVERLIGHT(亿光)"))
      (libsource (lib "") (part "42-21A/GHC-YX1Y2N/1T"))
    )
    (comp (ref "LED208")
      (value "42-21A/GHC-YX1Y2N/1T")
      (fields (field (name "Manufacturer") "EVERLIGHT(亿光)"))
      (libsource (lib "") (part "42-21A/GHC-YX1Y2N/1T"))
    )
    (comp (ref "LED209")
      (value "42-21A/GHC-YX1Y2N/1T")
      (fields (field (name "Manufacturer") "EVERLIGHT(亿光)"))
      (libsource (lib "") (part "42-21A/GHC-YX1Y2N/1T"))
    )
    (comp (ref "LED210")
      (value "42-21A/GHC-YX1Y2N/1T")
      (fields (field (name "Manufacturer") "EVERLIGHT(亿光)"))
      (libsource (lib "") (part "42-21A/GHC-YX1Y2N/1T"))
    )
    (comp (ref "LED211")
      (value "42-21A/GHC-YX1Y2N/1T")
      (fields (field (name "Manufacturer") "EVERLIGHT(亿光)"))
      (libsource (lib "") (part "42-21A/GHC-YX1Y2N/1T"))
    )
    (comp (ref "LED212")
      (value "42-21A/GHC-YX1Y2N/1T")
      (fields (field (name "Manufacturer") "EVERLIGHT(亿光)"))
      (libsource (lib "") (part "42-21A/GHC-YX1Y2N/1T"))
    )
    (comp (ref "LED213")
      (value "42-21A/GHC-YX1Y2N/1T")
      (fields (field (name "Manufacturer") "EVERLIGHT(亿光)"))
      (libsource (lib "") (part "42-21A/GHC-YX1Y2N/1T"))
    )
    (comp (ref "LED214")
      (value "42-21A/GHC-YX1Y2N/1T")
      (fields (field (name "Manufacturer") "EVERLIGHT(亿光)"))
      (libsource (lib "") (part "42-21A/GHC-YX1Y2N/1T"))
    )
    (comp (ref "LED215")
      (value "42-21A/GHC-YX1Y2N/1T")
      (fields (field (name "Manufacturer") "EVERLIGHT(亿光)"))
      (libsource (lib "") (part "42-21A/GHC-YX1Y2N/1T"))
    )
    (comp (ref "LED216")
      (value "42-21A/GHC-YX1Y2N/1T")
      (fields (field (name "Manufacturer") "EVERLIGHT(亿光)"))
      (libsource (lib "") (part "42-21A/GHC-YX1Y2N/1T"))
    )
    (comp (ref "LED217")
      (value "42-21A/GHC-YX1Y2N/1T")
      (fields (field (name "Manufacturer") "EVERLIGHT(亿光)"))
      (libsource (lib "") (part "42-21A/GHC-YX1Y2N/1T"))
    )
    (comp (ref "LED218")
      (value "42-21A/GHC-YX1Y2N/1T")
      (fields (field (name "Manufacturer") "EVERLIGHT(亿光)"))
      (libsource (lib "") (part "42-21A/GHC-YX1Y2N/1T"))
    )
    (comp (ref "LED219")
      (value "42-21A/GHC-YX1Y2N/1T")
      (fields (field (name "Manufacturer") "EVERLIGHT(亿光)"))
      (libsource (lib "") (part "42-21A/GHC-YX1Y2N/1T"))
    )
    (comp (ref "LED220")
      (value "42-21A/GHC-YX1Y2N/1T")
      (fields (field (name "Manufacturer") "EVERLIGHT(亿光)"))
      (libsource (lib "") (part "42-21A/GHC-YX1Y2N/1T"))
    )
    (comp (ref "LED221")
      (value "42-21A/GHC-YX1Y2N/1T")
      (fields (field (name "Manufacturer") "EVERLIGHT(亿光)"))
      (libsource (lib "") (part "42-21A/GHC-YX1Y2N/1T"))
    )
    (comp (ref "LED222")
      (value "42-21A/GHC-YX1Y2N/1T")
      (fields (field (name "Manufacturer") "EVERLIGHT(亿光)"))
      (libsource (lib "") (part "42-21A/GHC-YX1Y2N/1T"))
    )
    (comp (ref "LED223")
      (value "42-21A/GHC-YX1Y2N/1T")
      (fields (field (name "Manufacturer") "EVERLIGHT(亿光)"))
      (libsource (lib "") (part "42-21A/GHC-YX1Y2N/1T"))
    )
    (comp (ref "LED224")
      (value "42-21A/GHC-YX1Y2N/1T")
      (fields (field (name "Manufacturer") "EVERLIGHT(亿光)"))
      (libsource (lib "") (part "42-21A/GHC-YX1Y2N/1T"))
    )
    (comp (ref "LED225")
      (value "42-21A/GHC-YX1Y2N/1T")
      (fields (field (name "Manufacturer") "EVERLIGHT(亿光)"))
      (libsource (lib "") (part "42-21A/GHC-YX1Y2N/1T"))
    )
    (comp (ref "LED226")
      (value "42-21A/GHC-YX1Y2N/1T")
      (fields (field (name "Manufacturer") "EVERLIGHT(亿光)"))
      (libsource (lib "") (part "42-21A/GHC-YX1Y2N/1T"))
    )
    (comp (ref "LED227")
      (value "42-21A/GHC-YX1Y2N/1T")
      (fields (field (name "Manufacturer") "EVERLIGHT(亿光)"))
      (libsource (lib "") (part "42-21A/GHC-YX1Y2N/1T"))
    )
    (comp (ref "LED228")
      (value "42-21A/GHC-YX1Y2N/1T")
      (fields (field (name "Manufacturer") "EVERLIGHT(亿光)"))
      (libsource (lib "") (part "42-21A/GHC-YX1Y2N/1T"))
    )
    (comp (ref "LED229")
      (value "42-21A/GHC-YX1Y2N/1T")
      (fields (field (name "Manufacturer") "EVERLIGHT(亿光)"))
      (libsource (lib "") (part "42-21A/GHC-YX1Y2N/1T"))
    )
    (comp (ref "LED230")
      (value "42-21A/GHC-YX1Y2N/1T")
      (fields (field (name "Manufacturer") "EVERLIGHT(亿光)"))
      (libsource (lib "") (part "42-21A/GHC-YX1Y2N/1T"))
    )
    (comp (ref "LED231")
      (value "42-21A/GHC-YX1Y2N/1T")
      (fields (field (name "Manufacturer") "EVERLIGHT(亿光)"))
      (libsource (lib "") (part "42-21A/GHC-YX1Y2N/1T"))
    )
    (comp (ref "LED232")
      (value "42-21A/GHC-YX1Y2N/1T")
      (fields (field (name "Manufacturer") "EVERLIGHT(亿光)"))
      (libsource (lib "") (part "42-21A/GHC-YX1Y2N/1T"))
    )
    (comp (ref "LED233")
      (value "42-21A/GHC-YX1Y2N/1T")
      (fields (field (name "Manufacturer") "EVERLIGHT(亿光)"))
      (libsource (lib "") (part "42-21A/GHC-YX1Y2N/1T"))
    )
    (comp (ref "LED234")
      (value "42-21A/GHC-YX1Y2N/1T")
      (fields (field (name "Manufacturer") "EVERLIGHT(亿光)"))
      (libsource (lib "") (part "42-21A/GHC-YX1Y2N/1T"))
    )
    (comp (ref "LED235")
      (value "42-21A/GHC-YX1Y2N/1T")
      (fields (field (name "Manufacturer") "EVERLIGHT(亿光)"))
      (libsource (lib "") (part "42-21A/GHC-YX1Y2N/1T"))
    )
    (comp (ref "LED236")
      (value "42-21A/GHC-YX1Y2N/1T")
      (fields (field (name "Manufacturer") "EVERLIGHT(亿光)"))
      (libsource (lib "") (part "42-21A/GHC-YX1Y2N/1T"))
    )
    (comp (ref "LED237")
      (value "42-21A/GHC-YX1Y2N/1T")
      (fields (field (name "Manufacturer") "EVERLIGHT(亿光)"))
      (libsource (lib "") (part "42-21A/GHC-YX1Y2N/1T"))
    )
    (comp (ref "LED238")
      (value "42-21A/GHC-YX1Y2N/1T")
      (fields (field (name "Manufacturer") "EVERLIGHT(亿光)"))
      (libsource (lib "") (part "42-21A/GHC-YX1Y2N/1T"))
    )
    (comp (ref "LED239")
      (value "42-21A/GHC-YX1Y2N/1T")
      (fields (field (name "Manufacturer") "EVERLIGHT(亿光)"))
      (libsource (lib "") (part "42-21A/GHC-YX1Y2N/1T"))
    )
    (comp (ref "LED240")
      (value "42-21A/GHC-YX1Y2N/1T")
      (fields (field (name "Manufacturer") "EVERLIGHT(亿光)"))
      (libsource (lib "") (part "42-21A/GHC-YX1Y2N/1T"))
    )
    (comp (ref "LED241")
      (value "42-21A/GHC-YX1Y2N/1T")
      (fields (field (name "Manufacturer") "EVERLIGHT(亿光)"))
      (libsource (lib "") (part "42-21A/GHC-YX1Y2N/1T"))
    )
    (comp (ref "LED242")
      (value "42-21A/GHC-YX1Y2N/1T")
      (fields (field (name "Manufacturer") "EVERLIGHT(亿光)"))
      (libsource (lib "") (part "42-21A/GHC-YX1Y2N/1T"))
    )
    (comp (ref "LED243")
      (value "42-21A/GHC-YX1Y2N/1T")
      (fields (field (name "Manufacturer") "EVERLIGHT(亿光)"))
      (libsource (lib "") (part "42-21A/GHC-YX1Y2N/1T"))
    )
    (comp (ref "LED244")
      (value "42-21A/GHC-YX1Y2N/1T")
      (fields (field (name "Manufacturer") "EVERLIGHT(亿光)"))
      (libsource (lib "") (part "42-21A/GHC-YX1Y2N/1T"))
    )
    (comp (ref "LED245")
      (value "42-21A/GHC-YX1Y2N/1T")
      (fields (field (name "Manufacturer") "EVERLIGHT(亿光)"))
      (libsource (lib "") (part "42-21A/GHC-YX1Y2N/1T"))
    )
    (comp (ref "LED246")
      (value "42-21A/GHC-YX1Y2N/1T")
      (fields (field (name "Manufacturer") "EVERLIGHT(亿光)"))
      (libsource (lib "") (part "42-21A/GHC-YX1Y2N/1T"))
    )
    (comp (ref "LED247")
      (value "42-21A/GHC-YX1Y2N/1T")
      (fields (field (name "Manufacturer") "EVERLIGHT(亿光)"))
      (libsource (lib "") (part "42-21A/GHC-YX1Y2N/1T"))
    )
    (comp (ref "LED248")
      (value "42-21A/GHC-YX1Y2N/1T")
      (fields (field (name "Manufacturer") "EVERLIGHT(亿光)"))
      (libsource (lib "") (part "42-21A/GHC-YX1Y2N/1T"))
    )
    (comp (ref "LED249")
      (value "42-21A/GHC-YX1Y2N/1T")
      (fields (field (name "Manufacturer") "EVERLIGHT(亿光)"))
      (libsource (lib "") (part "42-21A/GHC-YX1Y2N/1T"))
    )
    (comp (ref "LED250")
      (value "42-21A/GHC-YX1Y2N/1T")
      (fields (field (name "Manufacturer") "EVERLIGHT(亿光)"))
      (libsource (lib "") (part "42-21A/GHC-YX1Y2N/1T"))
    )
    (comp (ref "LED251")
      (value "42-21A/GHC-YX1Y2N/1T")
      (fields (field (name "Manufacturer") "EVERLIGHT(亿光)"))
      (libsource (lib "") (part "42-21A/GHC-YX1Y2N/1T"))
    )
    (comp (ref "LED252")
      (value "42-21A/GHC-YX1Y2N/1T")
      (fields (field (name "Manufacturer") "EVERLIGHT(亿光)"))
      (libsource (lib "") (part "42-21A/GHC-YX1Y2N/1T"))
    )
    (comp (ref "LED253")
      (value "42-21A/GHC-YX1Y2N/1T")
      (fields (field (name "Manufacturer") "EVERLIGHT(亿光)"))
      (libsource (lib "") (part "42-21A/GHC-YX1Y2N/1T"))
    )
    (comp (ref "LED254")
      (value "42-21A/GHC-YX1Y2N/1T")
      (fields (field (name "Manufacturer") "EVERLIGHT(亿光)"))
      (libsource (lib "") (part "42-21A/GHC-YX1Y2N/1T"))
    )
    (comp (ref "LED255")
      (value "42-21A/GHC-YX1Y2N/1T")
      (fields (field (name "Manufacturer") "EVERLIGHT(亿光)"))
      (libsource (lib "") (part "42-21A/GHC-YX1Y2N/1T"))
    )
    (comp (ref "LED256")
      (value "42-21A/GHC-YX1Y2N/1T")
      (fields (field (name "Manufacturer") "EVERLIGHT(亿光)"))
      (libsource (lib "") (part "42-21A/GHC-YX1Y2N/1T"))
    )
    (comp (ref "Q17")
      (value "2N7000-TA")
      (fields (field (name "Manufacturer") "CJ(江苏长电/长晶)"))
      (libsource (lib "") (part "2N7000-TA"))
    )
    (comp (ref "Q18")
      (value "IRLZ44NPBF-MNS")
      (fields (field (name "Manufacturer") "minos(迈诺斯)"))
      (libsource (lib "") (part "IRLZ44NPBF-MNS"))
    )
    (comp (ref "Q19")
      (value "IRLZ44NPBF-MNS")
      (fields (field (name "Manufacturer") "minos(迈诺斯)"))
      (libsource (lib "") (part "IRLZ44NPBF-MNS"))
    )
    (comp (ref "Q20")
      (value "IRLZ44NPBF-MNS")
      (fields (field (name "Manufacturer") "minos(迈诺斯)"))
      (libsource (lib "") (part "IRLZ44NPBF-MNS"))
    )
    (comp (ref "Q21")
      (value "IRLZ44NPBF-MNS")
      (fields (field (name "Manufacturer") "minos(迈诺斯)"))
      (libsource (lib "") (part "IRLZ44NPBF-MNS"))
    )
    (comp (ref "Q22")
      (value "IRLZ44NPBF-MNS")
      (fields (field (name "Manufacturer") "minos(迈诺斯)"))
      (libsource (lib "") (part "IRLZ44NPBF-MNS"))
    )
    (comp (ref "Q23")
      (value "IRLZ44NPBF-MNS")
      (fields (field (name "Manufacturer") "minos(迈诺斯)"))
      (libsource (lib "") (part "IRLZ44NPBF-MNS"))
    )
    (comp (ref "Q24")
      (value "IRLZ44NPBF-MNS")
      (fields (field (name "Manufacturer") "minos(迈诺斯)"))
      (libsource (lib "") (part "IRLZ44NPBF-MNS"))
    )
    (comp (ref "Q25")
      (value "IRLZ44NPBF-MNS")
      (fields (field (name "Manufacturer") "minos(迈诺斯)"))
      (libsource (lib "") (part "IRLZ44NPBF-MNS"))
    )
    (comp (ref "Q26")
      (value "IRLZ44NPBF-MNS")
      (fields (field (name "Manufacturer") "minos(迈诺斯)"))
      (libsource (lib "") (part "IRLZ44NPBF-MNS"))
    )
    (comp (ref "Q27")
      (value "IRLZ44NPBF-MNS")
      (fields (field (name "Manufacturer") "minos(迈诺斯)"))
      (libsource (lib "") (part "IRLZ44NPBF-MNS"))
    )
    (comp (ref "Q28")
      (value "IRLZ44NPBF-MNS")
      (fields (field (name "Manufacturer") "minos(迈诺斯)"))
      (libsource (lib "") (part "IRLZ44NPBF-MNS"))
    )
    (comp (ref "Q29")
      (value "IRLZ44NPBF-MNS")
      (fields (field (name "Manufacturer") "minos(迈诺斯)"))
      (libsource (lib "") (part "IRLZ44NPBF-MNS"))
    )
    (comp (ref "Q30")
      (value "IRLZ44NPBF-MNS")
      (fields (field (name "Manufacturer") "minos(迈诺斯)"))
      (libsource (lib "") (part "IRLZ44NPBF-MNS"))
    )
    (comp (ref "Q31")
      (value "IRLZ44NPBF-MNS")
      (fields (field (name "Manufacturer") "minos(迈诺斯)"))
      (libsource (lib "") (part "IRLZ44NPBF-MNS"))
    )
    (comp (ref "Q32")
      (value "IRLZ44NPBF-MNS")
      (fields (field (name "Manufacturer") "minos(迈诺斯)"))
      (libsource (lib "") (part "IRLZ44NPBF-MNS"))
    )
    (comp (ref "Q33")
      (value "IRLZ44NPBF-MNS")
      (fields (field (name "Manufacturer") "minos(迈诺斯)"))
      (libsource (lib "") (part "IRLZ44NPBF-MNS"))
    )
    (comp (ref "R1")
      (value "10k")
      (fields (field (name "Manufacturer Part") "MFR-12FTF52-10K") (field (name "Manufacturer") "YAGEO(国巨)"))
      (libsource (lib "") (part "R_0603_EU_1"))
    )
    (comp (ref "R2")
      (value "10k")
      (fields (field (name "Manufacturer Part") "MFR-12FTF52-10K") (field (name "Manufacturer") "YAGEO(国巨)"))
      (libsource (lib "") (part "R_0603_EU_1"))
    )
    (comp (ref "R3")
      (value "10k")
      (fields (field (name "Manufacturer Part") "MFR-12FTF52-10K") (field (name "Manufacturer") "YAGEO(国巨)"))
      (libsource (lib "") (part "R_0603_EU_1"))
    )
    (comp (ref "R4")
      (value "10k")
      (fields (field (name "Manufacturer Part") "MFR-12FTF52-10K") (field (name "Manufacturer") "YAGEO(国巨)"))
      (libsource (lib "") (part "R_0603_EU_1"))
    )
    (comp (ref "R5")
      (value "10k")
      (fields (field (name "Manufacturer Part") "MFR-12FTF52-10K") (field (name "Manufacturer") "YAGEO(国巨)"))
      (libsource (lib "") (part "R_0603_EU_1"))
    )
    (comp (ref "R6")
      (value "10k")
      (fields (field (name "Manufacturer Part") "MFR-12FTF52-10K") (field (name "Manufacturer") "YAGEO(国巨)"))
      (libsource (lib "") (part "R_0603_EU_1"))
    )
    (comp (ref "R7")
      (value "10k")
      (fields (field (name "Manufacturer Part") "MFR-12FTF52-10K") (field (name "Manufacturer") "YAGEO(国巨)"))
      (libsource (lib "") (part "R_0603_EU_1"))
    )
    (comp (ref "R8")
      (value "10k")
      (fields (field (name "Manufacturer Part") "MFR-12FTF52-10K") (field (name "Manufacturer") "YAGEO(国巨)"))
      (libsource (lib "") (part "R_0603_EU_1"))
    )
    (comp (ref "R9")
      (value "10k")
      (fields (field (name "Manufacturer Part") "MFR-12FTF52-10K") (field (name "Manufacturer") "YAGEO(国巨)"))
      (libsource (lib "") (part "R_0603_EU_1"))
    )
    (comp (ref "R10")
      (value "10k")
      (fields (field (name "Manufacturer Part") "MFR-12FTF52-10K") (field (name "Manufacturer") "YAGEO(国巨)"))
      (libsource (lib "") (part "R_0603_EU_1"))
    )
    (comp (ref "R11")
      (value "10k")
      (fields (field (name "Manufacturer Part") "MFR-12FTF52-10K") (field (name "Manufacturer") "YAGEO(国巨)"))
      (libsource (lib "") (part "R_0603_EU_1"))
    )
    (comp (ref "R12")
      (value "10k")
      (fields (field (name "Manufacturer Part") "MFR-12FTF52-10K") (field (name "Manufacturer") "YAGEO(国巨)"))
      (libsource (lib "") (part "R_0603_EU_1"))
    )
    (comp (ref "R13")
      (value "10k")
      (fields (field (name "Manufacturer Part") "MFR-12FTF52-10K") (field (name "Manufacturer") "YAGEO(国巨)"))
      (libsource (lib "") (part "R_0603_EU_1"))
    )
    (comp (ref "R14")
      (value "10k")
      (fields (field (name "Manufacturer Part") "MFR-12FTF52-10K") (field (name "Manufacturer") "YAGEO(国巨)"))
      (libsource (lib "") (part "R_0603_EU_1"))
    )
    (comp (ref "R15")
      (value "10k")
      (fields (field (name "Manufacturer Part") "MFR-12FTF52-10K") (field (name "Manufacturer") "YAGEO(国巨)"))
      (libsource (lib "") (part "R_0603_EU_1"))
    )
    (comp (ref "R16")
      (value "10k")
      (fields (field (name "Manufacturer Part") "MFR-12FTF52-10K") (field (name "Manufacturer") "YAGEO(国巨)"))
      (libsource (lib "") (part "R_0603_EU_1"))
    )
    (comp (ref "R17")
      (value "10k")
      (fields (field (name "Manufacturer Part") "MFR-12FTF52-10K") (field (name "Manufacturer") "YAGEO(国巨)"))
      (libsource (lib "") (part "R_0603_EU"))
    )
    (comp (ref "R18")
      (value "10k")
      (fields (field (name "Manufacturer Part") "MFR-12FTF52-10K") (field (name "Manufacturer") "YAGEO(国巨)"))
      (libsource (lib "") (part "R_0603_EU"))
    )
    (comp (ref "R19")
      (value "10k")
      (fields (field (name "Manufacturer Part") "MFR-12FTF52-10K") (field (name "Manufacturer") "YAGEO(国巨)"))
      (libsource (lib "") (part "R_0603_EU_1"))
    )
    (comp (ref "R20")
      (value "10k")
      (fields (field (name "Manufacturer Part") "MFR-12FTF52-10K") (field (name "Manufacturer") "YAGEO(国巨)"))
      (libsource (lib "") (part "R_0603_EU"))
    )
    (comp (ref "R21")
      (value "1M")
      (fields (field (name "Manufacturer Part") "FRC2512F1004TS") (field (name "Manufacturer") "FOJAN(富捷)"))
      (libsource (lib "") (part "R_0603_EU"))
    )
    (comp (ref "R22")
      (value "2.2k")
      (fields (field (name "Manufacturer Part") "MF0204FTE52-2K2") (field (name "Manufacturer") "YAGEO(国巨)"))
      (libsource (lib "") (part "R_0603_EU_1"))
    )
    (comp (ref "R23")
      (value "10k")
      (fields (field (name "Manufacturer Part") "MFR-12FTF52-10K") (field (name "Manufacturer") "YAGEO(国巨)"))
      (libsource (lib "") (part "R_0603_EU"))
    )
    (comp (ref "R24")
      (value "10k")
      (fields (field (name "Manufacturer Part") "MFR-12FTF52-10K") (field (name "Manufacturer") "YAGEO(国巨)"))
      (libsource (lib "") (part "R_0603_EU"))
    )
    (comp (ref "R25")
      (value "10k")
      (fields (field (name "Manufacturer Part") "MFR-12FTF52-10K") (field (name "Manufacturer") "YAGEO(国巨)"))
      (libsource (lib "") (part "R_0603_EU"))
    )
    (comp (ref "R26")
      (value "10k")
      (fields (field (name "Manufacturer Part") "MFR-12FTF52-10K") (field (name "Manufacturer") "YAGEO(国巨)"))
      (libsource (lib "") (part "R_0603_EU"))
    )
    (comp (ref "R27")
      (value "10k")
      (fields (field (name "Manufacturer Part") "MFR-12FTF52-10K") (field (name "Manufacturer") "YAGEO(国巨)"))
      (libsource (lib "") (part "R_0603_EU"))
    )
    (comp (ref "R28")
      (value "10k")
      (fields (field (name "Manufacturer Part") "MFR-12FTF52-10K") (field (name "Manufacturer") "YAGEO(国巨)"))
      (libsource (lib "") (part "R_0603_EU"))
    )
    (comp (ref "R29")
      (value "10k")
      (fields (field (name "Manufacturer Part") "MFR-12FTF52-10K") (field (name "Manufacturer") "YAGEO(国巨)"))
      (libsource (lib "") (part "R_0603_EU"))
    )
    (comp (ref "R30")
      (value "10k")
      (fields (field (name "Manufacturer Part") "MFR-12FTF52-10K") (field (name "Manufacturer") "YAGEO(国巨)"))
      (libsource (lib "") (part "R_0603_EU"))
    )
    (comp (ref "R31")
      (value "10k")
      (fields (field (name "Manufacturer Part") "MFR-12FTF52-10K") (field (name "Manufacturer") "YAGEO(国巨)"))
      (libsource (lib "") (part "R_0603_EU"))
    )
    (comp (ref "R32")
      (value "10k")
      (fields (field (name "Manufacturer Part") "MFR-12FTF52-10K") (field (name "Manufacturer") "YAGEO(国巨)"))
      (libsource (lib "") (part "R_0603_EU"))
    )
    (comp (ref "R33")
      (value "10k")
      (fields (field (name "Manufacturer Part") "MFR-12FTF52-10K") (field (name "Manufacturer") "YAGEO(国巨)"))
      (libsource (lib "") (part "R_0603_EU"))
    )
    (comp (ref "R34")
      (value "10k")
      (fields (field (name "Manufacturer Part") "MFR-12FTF52-10K") (field (name "Manufacturer") "YAGEO(国巨)"))
      (libsource (lib "") (part "R_0603_EU"))
    )
    (comp (ref "R35")
      (value "10k")
      (fields (field (name "Manufacturer Part") "MFR-12FTF52-10K") (field (name "Manufacturer") "YAGEO(国巨)"))
      (libsource (lib "") (part "R_0603_EU"))
    )
    (comp (ref "R36")
      (value "10k")
      (fields (field (name "Manufacturer Part") "MFR-12FTF52-10K") (field (name "Manufacturer") "YAGEO(国巨)"))
      (libsource (lib "") (part "R_0603_EU"))
    )
    (comp (ref "R37")
      (value "10k")
      (fields (field (name "Manufacturer Part") "MFR-12FTF52-10K") (field (name "Manufacturer") "YAGEO(国巨)"))
      (libsource (lib "") (part "R_0603_EU"))
    )
    (comp (ref "SW1")
      (value "DIP switchEI-04")
      (fields (field (name "Manufacturer Part") "拨码开关EI-04") (field (name "Manufacturer") "圜达"))
      (libsource (lib "") (part "DIP switchEI-04"))
    )
    (comp (ref "U1")
      (value "HT74HC154ARWZ")
      (fields (field (name "Manufacturer") "HTCSEMI(海天芯)"))
      (libsource (lib "") (part "HT74HC154ARWZ"))
    )
    (comp (ref "U2")
      (value "CD74HC4060M96")
      (fields (field (name "Manufacturer") "TI(德州仪器)"))
      (libsource (lib "") (part "CD74HC4060M96"))
    )
    (comp (ref "U3")
      (value "74LVC541AD-Q100J")
      (fields (field (name "Manufacturer") "Nexperia(安世)"))
      (libsource (lib "") (part "74LVC541AD-Q100J"))
    )
    (comp (ref "U4")
      (value "SN74HC590ADR")
      (fields (field (name "Manufacturer") "TI(德州仪器)"))
      (libsource (lib "") (part "SN74HC590ADR"))
    )
    (comp (ref "U5")
      (value "74LVC541AD-Q100J")
      (fields (field (name "Manufacturer") "Nexperia(安世)"))
      (libsource (lib "") (part "74LVC541AD-Q100J"))
    )
    (comp (ref "U6")
      (value "AT28C256-15PU")
      (fields (field (name "Manufacturer") "MICROCHIP(美国微芯)"))
      (libsource (lib "") (part "AT28C256-15PU"))
    )
    (comp (ref "U7")
      (value "LM3940IMPX-3.3/NOPB")
      (fields (field (name "Manufacturer") "TI(德州仪器)"))
      (libsource (lib "") (part "LM3940IMPX-3.3/NOPB"))
    )
    (comp (ref "U8")
      (value "15Ω")
      (fields (field (name "Manufacturer Part") "MF1W-15Ω±1%-6T52") (field (name "Manufacturer") "VO(翔胜)"))
      (libsource (lib "") (part "MF1W-15Ω±1%-6T52"))
    )
    (comp (ref "U9")
      (value "15Ω")
      (fields (field (name "Manufacturer Part") "MF1W-15Ω±1%-6T52") (field (name "Manufacturer") "VO(翔胜)"))
      (libsource (lib "") (part "MF1W-15Ω±1%-6T52"))
    )
    (comp (ref "U10")
      (value "15Ω")
      (fields (field (name "Manufacturer Part") "MF1W-15Ω±1%-6T52") (field (name "Manufacturer") "VO(翔胜)"))
      (libsource (lib "") (part "MF1W-15Ω±1%-6T52"))
    )
    (comp (ref "U11")
      (value "15Ω")
      (fields (field (name "Manufacturer Part") "MF1W-15Ω±1%-6T52") (field (name "Manufacturer") "VO(翔胜)"))
      (libsource (lib "") (part "MF1W-15Ω±1%-6T52"))
    )
    (comp (ref "U12")
      (value "15Ω")
      (fields (field (name "Manufacturer Part") "MF1W-15Ω±1%-6T52") (field (name "Manufacturer") "VO(翔胜)"))
      (libsource (lib "") (part "MF1W-15Ω±1%-6T52"))
    )
    (comp (ref "U13")
      (value "15Ω")
      (fields (field (name "Manufacturer Part") "MF1W-15Ω±1%-6T52") (field (name "Manufacturer") "VO(翔胜)"))
      (libsource (lib "") (part "MF1W-15Ω±1%-6T52"))
    )
    (comp (ref "U14")
      (value "15Ω")
      (fields (field (name "Manufacturer Part") "MF1W-15Ω±1%-6T52") (field (name "Manufacturer") "VO(翔胜)"))
      (libsource (lib "") (part "MF1W-15Ω±1%-6T52"))
    )
    (comp (ref "U15")
      (value "15Ω")
      (fields (field (name "Manufacturer Part") "MF1W-15Ω±1%-6T52") (field (name "Manufacturer") "VO(翔胜)"))
      (libsource (lib "") (part "MF1W-15Ω±1%-6T52"))
    )
    (comp (ref "U16")
      (value "15Ω")
      (fields (field (name "Manufacturer Part") "MF1W-15Ω±1%-6T52") (field (name "Manufacturer") "VO(翔胜)"))
      (libsource (lib "") (part "MF1W-15Ω±1%-6T52"))
    )
    (comp (ref "U17")
      (value "15Ω")
      (fields (field (name "Manufacturer Part") "MF1W-15Ω±1%-6T52") (field (name "Manufacturer") "VO(翔胜)"))
      (libsource (lib "") (part "MF1W-15Ω±1%-6T52"))
    )
    (comp (ref "U18")
      (value "15Ω")
      (fields (field (name "Manufacturer Part") "MF1W-15Ω±1%-6T52") (field (name "Manufacturer") "VO(翔胜)"))
      (libsource (lib "") (part "MF1W-15Ω±1%-6T52"))
    )
    (comp (ref "U19")
      (value "15Ω")
      (fields (field (name "Manufacturer Part") "MF1W-15Ω±1%-6T52") (field (name "Manufacturer") "VO(翔胜)"))
      (libsource (lib "") (part "MF1W-15Ω±1%-6T52"))
    )
    (comp (ref "U20")
      (value "15Ω")
      (fields (field (name "Manufacturer Part") "MF1W-15Ω±1%-6T52") (field (name "Manufacturer") "VO(翔胜)"))
      (libsource (lib "") (part "MF1W-15Ω±1%-6T52"))
    )
    (comp (ref "U21")
      (value "15Ω")
      (fields (field (name "Manufacturer Part") "MF1W-15Ω±1%-6T52") (field (name "Manufacturer") "VO(翔胜)"))
      (libsource (lib "") (part "MF1W-15Ω±1%-6T52"))
    )
    (comp (ref "U22")
      (value "15Ω")
      (fields (field (name "Manufacturer Part") "MF1W-15Ω±1%-6T52") (field (name "Manufacturer") "VO(翔胜)"))
      (libsource (lib "") (part "MF1W-15Ω±1%-6T52"))
    )
    (comp (ref "U23")
      (value "15Ω")
      (fields (field (name "Manufacturer Part") "MF1W-15Ω±1%-6T52") (field (name "Manufacturer") "VO(翔胜)"))
      (libsource (lib "") (part "MF1W-15Ω±1%-6T52"))
    )
    (comp (ref "X1")
      (value "32.768kHz")
      (fields
        (field (name "Manufacturer Part") "CD02K032768ACNBAEAE")
        (field (name "Manufacturer") "TKD(泰晶)")
      )
      (libsource (lib "") (part "CD02K032768ACNBAEAE"))
    )
  )
  (nets
    (net (code "1") (name "+3.3V") (class "Default")
      (node (ref "C6") (pin "1") (pinfunction "1_1") (pintype "unspecified"))
      (node (ref "R1") (pin "1") (pinfunction "1_1") (pintype "unspecified"))
      (node (ref "R10") (pin "1") (pinfunction "1_1") (pintype "unspecified"))
      (node (ref "R11") (pin "1") (pinfunction "1_1") (pintype "unspecified"))
      (node (ref "R12") (pin "1") (pinfunction "1_1") (pintype "unspecified"))
      (node (ref "R13") (pin "1") (pinfunction "1_1") (pintype "unspecified"))
      (node (ref "R14") (pin "1") (pinfunction "1_1") (pintype "unspecified"))
      (node (ref "R15") (pin "1") (pinfunction "1_1") (pintype "unspecified"))
      (node (ref "R16") (pin "1") (pinfunction "1_1") (pintype "unspecified"))
      (node (ref "R18") (pin "2") (pinfunction "2_2") (pintype "unspecified"))
      (node (ref "R2") (pin "1") (pinfunction "1_1") (pintype "unspecified"))
      (node (ref "R3") (pin "1") (pinfunction "1_1") (pintype "unspecified"))
      (node (ref "R4") (pin "1") (pinfunction "1_1") (pintype "unspecified"))
      (node (ref "R5") (pin "1") (pinfunction "1_1") (pintype "unspecified"))
      (node (ref "R6") (pin "1") (pinfunction "1_1") (pintype "unspecified"))
      (node (ref "R7") (pin "1") (pinfunction "1_1") (pintype "unspecified"))
      (node (ref "R8") (pin "1") (pinfunction "1_1") (pintype "unspecified"))
      (node (ref "R9") (pin "1") (pinfunction "1_1") (pintype "unspecified"))
      (node (ref "U3") (pin "20") (pinfunction "VCC_20") (pintype "unspecified"))
      (node (ref "U5") (pin "20") (pinfunction "VCC_20") (pintype "unspecified"))
      (node (ref "U7") (pin "4") (pinfunction "GND_4") (pintype "unspecified"))
    )
    (net (code "2") (name "+5V") (class "Default")
      (node (ref "C1") (pin "2") (pinfunction "2_2") (pintype "unspecified"))
      (node (ref "C2") (pin "2") (pinfunction "2_2") (pintype "unspecified"))
      (node (ref "C5") (pin "1") (pinfunction "1_1") (pintype "input"))
      (node (ref "DIP1") (pin "1") (pinfunction "1_1") (pintype "unspecified"))
      (node (ref "DIP1") (pin "2") (pinfunction "2_2") (pintype "unspecified"))
      (node (ref "DIP1") (pin "3") (pinfunction "3_3") (pintype "unspecified"))
      (node (ref "DIP1") (pin "4") (pinfunction "4_4") (pintype "unspecified"))
      (node (ref "DIP1") (pin "5") (pinfunction "5_5") (pintype "unspecified"))
      (node (ref "DIP1") (pin "6") (pinfunction "6_6") (pintype "unspecified"))
      (node (ref "DIP1") (pin "7") (pinfunction "7_7") (pintype "unspecified"))
      (node (ref "DIP1") (pin "8") (pinfunction "8_8") (pintype "unspecified"))
      (node (ref "J3") (pin "2") (pinfunction "2_2") (pintype "unspecified"))
      (node (ref "R20") (pin "2") (pinfunction "2_2") (pintype "unspecified"))
      (node (ref "R23") (pin "2") (pinfunction "2_2") (pintype "unspecified"))
      (node (ref "SW1") (pin "1") (pinfunction "1_1") (pintype "unspecified"))
      (node (ref "SW1") (pin "2") (pinfunction "2_2") (pintype "unspecified"))
      (node (ref "SW1") (pin "3") (pinfunction "3_3") (pintype "unspecified"))
      (node (ref "SW1") (pin "4") (pinfunction "4_4") (pintype "unspecified"))
      (node (ref "U1") (pin "24") (pinfunction "VCC_24") (pintype "unspecified"))
      (node (ref "U2") (pin "16") (pinfunction "VCC_16") (pintype "unspecified"))
      (node (ref "U4") (pin "16") (pinfunction "VCC_16") (pintype "unspecified"))
      (node (ref "U6") (pin "28") (pinfunction "Vcc_28") (pintype "unspecified"))
      (node (ref "U7") (pin "1") (pinfunction "IN_1") (pintype "unspecified"))
    )
    (net (code "3") (name "1") (class "Default")
      (node (ref "LED1") (pin "2") (pinfunction "A_2") (pintype "unspecified"))
      (node (ref "LED10") (pin "2") (pinfunction "A_2") (pintype "unspecified"))
      (node (ref "LED11") (pin "2") (pinfunction "A_2") (pintype "unspecified"))
      (node (ref "LED12") (pin "2") (pinfunction "A_2") (pintype "unspecified"))
      (node (ref "LED13") (pin "2") (pinfunction "A_2") (pintype "unspecified"))
      (node (ref "LED14") (pin "2") (pinfunction "A_2") (pintype "unspecified"))
      (node (ref "LED15") (pin "2") (pinfunction "A_2") (pintype "unspecified"))
      (node (ref "LED16") (pin "2") (pinfunction "A_2") (pintype "unspecified"))
      (node (ref "LED2") (pin "2") (pinfunction "A_2") (pintype "unspecified"))
      (node (ref "LED3") (pin "2") (pinfunction "A_2") (pintype "unspecified"))
      (node (ref "LED4") (pin "2") (pinfunction "A_2") (pintype "unspecified"))
      (node (ref "LED5") (pin "2") (pinfunction "A_2") (pintype "unspecified"))
      (node (ref "LED6") (pin "2") (pinfunction "A_2") (pintype "unspecified"))
      (node (ref "LED7") (pin "2") (pinfunction "A_2") (pintype "unspecified"))
      (node (ref "LED8") (pin "2") (pinfunction "A_2") (pintype "unspecified"))
      (node (ref "LED9") (pin "2") (pinfunction "A_2") (pintype "unspecified"))
      (node (ref "U3") (pin "18") (pinfunction "Y0_18") (pintype "unspecified"))
    )
    (net (code "4") (name "2") (class "Default")
      (node (ref "LED17") (pin "2") (pinfunction "A_2") (pintype "unspecified"))
      (node (ref "LED18") (pin "2") (pinfunction "A_2") (pintype "unspecified"))
      (node (ref "LED19") (pin "2") (pinfunction "A_2") (pintype "unspecified"))
      (node (ref "LED20") (pin "2") (pinfunction "A_2") (pintype "unspecified"))
      (node (ref "LED21") (pin "2") (pinfunction "A_2") (pintype "unspecified"))
      (node (ref "LED22") (pin "2") (pinfunction "A_2") (pintype "unspecified"))
      (node (ref "LED23") (pin "2") (pinfunction "A_2") (pintype "unspecified"))
      (node (ref "LED24") (pin "2") (pinfunction "A_2") (pintype "unspecified"))
      (node (ref "LED25") (pin "2") (pinfunction "A_2") (pintype "unspecified"))
      (node (ref "LED26") (pin "2") (pinfunction "A_2") (pintype "unspecified"))
      (node (ref "LED27") (pin "2") (pinfunction "A_2") (pintype "unspecified"))
      (node (ref "LED28") (pin "2") (pinfunction "A_2") (pintype "unspecified"))
      (node (ref "LED29") (pin "2") (pinfunction "A_2") (pintype "unspecified"))
      (node (ref "LED30") (pin "2") (pinfunction "A_2") (pintype "unspecified"))
      (node (ref "LED31") (pin "2") (pinfunction "A_2") (pintype "unspecified"))
      (node (ref "LED32") (pin "2") (pinfunction "A_2") (pintype "unspecified"))
      (node (ref "U3") (pin "17") (pinfunction "Y1_17") (pintype "unspecified"))
    )
    (net (code "5") (name "3") (class "Default")
      (node (ref "LED33") (pin "2") (pinfunction "A_2") (pintype "unspecified"))
      (node (ref "LED34") (pin "2") (pinfunction "A_2") (pintype "unspecified"))
      (node (ref "LED35") (pin "2") (pinfunction "A_2") (pintype "unspecified"))
      (node (ref "LED36") (pin "2") (pinfunction "A_2") (pintype "unspecified"))
      (node (ref "LED37") (pin "2") (pinfunction "A_2") (pintype "unspecified"))
      (node (ref "LED38") (pin "2") (pinfunction "A_2") (pintype "unspecified"))
      (node (ref "LED39") (pin "2") (pinfunction "A_2") (pintype "unspecified"))
      (node (ref "LED40") (pin "2") (pinfunction "A_2") (pintype "unspecified"))
      (node (ref "LED41") (pin "2") (pinfunction "A_2") (pintype "unspecified"))
      (node (ref "LED42") (pin "2") (pinfunction "A_2") (pintype "unspecified"))
      (node (ref "LED43") (pin "2") (pinfunction "A_2") (pintype "unspecified"))
      (node (ref "LED44") (pin "2") (pinfunction "A_2") (pintype "unspecified"))
      (node (ref "LED45") (pin "2") (pinfunction "A_2") (pintype "unspecified"))
      (node (ref "LED46") (pin "2") (pinfunction "A_2") (pintype "unspecified"))
      (node (ref "LED47") (pin "2") (pinfunction "A_2") (pintype "unspecified"))
      (node (ref "LED48") (pin "2") (pinfunction "A_2") (pintype "unspecified"))
      (node (ref "U3") (pin "16") (pinfunction "Y2_16") (pintype "unspecified"))
    )
    (net (code "6") (name "4") (class "Default")
      (node (ref "LED49") (pin "2") (pinfunction "A_2") (pintype "unspecified"))
      (node (ref "LED50") (pin "2") (pinfunction "A_2") (pintype "unspecified"))
      (node (ref "LED51") (pin "2") (pinfunction "A_2") (pintype "unspecified"))
      (node (ref "LED52") (pin "2") (pinfunction "A_2") (pintype "unspecified"))
      (node (ref "LED53") (pin "2") (pinfunction "A_2") (pintype "unspecified"))
      (node (ref "LED54") (pin "2") (pinfunction "A_2") (pintype "unspecified"))
      (node (ref "LED55") (pin "2") (pinfunction "A_2") (pintype "unspecified"))
      (node (ref "LED56") (pin "2") (pinfunction "A_2") (pintype "unspecified"))
      (node (ref "LED57") (pin "2") (pinfunction "A_2") (pintype "unspecified"))
      (node (ref "LED58") (pin "2") (pinfunction "A_2") (pintype "unspecified"))
      (node (ref "LED59") (pin "2") (pinfunction "A_2") (pintype "unspecified"))
      (node (ref "LED60") (pin "2") (pinfunction "A_2") (pintype "unspecified"))
      (node (ref "LED61") (pin "2") (pinfunction "A_2") (pintype "unspecified"))
      (node (ref "LED62") (pin "2") (pinfunction "A_2") (pintype "unspecified"))
      (node (ref "LED63") (pin "2") (pinfunction "A_2") (pintype "unspecified"))
      (node (ref "LED64") (pin "2") (pinfunction "A_2") (pintype "unspecified"))
      (node (ref "U3") (pin "15") (pinfunction "Y3_15") (pintype "unspecified"))
    )
    (net (code "7") (name "5") (class "Default")
      (node (ref "LED65") (pin "2") (pinfunction "A_2") (pintype "unspecified"))
      (node (ref "LED66") (pin "2") (pinfunction "A_2") (pintype "unspecified"))
      (node (ref "LED67") (pin "2") (pinfunction "A_2") (pintype "unspecified"))
      (node (ref "LED68") (pin "2") (pinfunction "A_2") (pintype "unspecified"))
      (node (ref "LED69") (pin "2") (pinfunction "A_2") (pintype "unspecified"))
      (node (ref "LED70") (pin "2") (pinfunction "A_2") (pintype "unspecified"))
      (node (ref "LED71") (pin "2") (pinfunction "A_2") (pintype "unspecified"))
      (node (ref "LED72") (pin "2") (pinfunction "A_2") (pintype "unspecified"))
      (node (ref "LED73") (pin "2") (pinfunction "A_2") (pintype "unspecified"))
      (node (ref "LED74") (pin "2") (pinfunction "A_2") (pintype "unspecified"))
      (node (ref "LED75") (pin "2") (pinfunction "A_2") (pintype "unspecified"))
      (node (ref "LED76") (pin "2") (pinfunction "A_2") (pintype "unspecified"))
      (node (ref "LED77") (pin "2") (pinfunction "A_2") (pintype "unspecified"))
      (node (ref "LED78") (pin "2") (pinfunction "A_2") (pintype "unspecified"))
      (node (ref "LED79") (pin "2") (pinfunction "A_2") (pintype "unspecified"))
      (node (ref "LED80") (pin "2") (pinfunction "A_2") (pintype "unspecified"))
      (node (ref "U3") (pin "14") (pinfunction "Y4_14") (pintype "unspecified"))
    )
    (net (code "8") (name "6") (class "Default")
      (node (ref "LED81") (pin "2") (pinfunction "A_2") (pintype "unspecified"))
      (node (ref "LED82") (pin "2") (pinfunction "A_2") (pintype "unspecified"))
      (node (ref "LED83") (pin "2") (pinfunction "A_2") (pintype "unspecified"))
      (node (ref "LED84") (pin "2") (pinfunction "A_2") (pintype "unspecified"))
      (node (ref "LED85") (pin "2") (pinfunction "A_2") (pintype "unspecified"))
      (node (ref "LED86") (pin "2") (pinfunction "A_2") (pintype "unspecified"))
      (node (ref "LED87") (pin "2") (pinfunction "A_2") (pintype "unspecified"))
      (node (ref "LED88") (pin "2") (pinfunction "A_2") (pintype "unspecified"))
      (node (ref "LED89") (pin "2") (pinfunction "A_2") (pintype "unspecified"))
      (node (ref "LED90") (pin "2") (pinfunction "A_2") (pintype "unspecified"))
      (node (ref "LED91") (pin "2") (pinfunction "A_2") (pintype "unspecified"))
      (node (ref "LED92") (pin "2") (pinfunction "A_2") (pintype "unspecified"))
      (node (ref "LED93") (pin "2") (pinfunction "A_2") (pintype "unspecified"))
      (node (ref "LED94") (pin "2") (pinfunction "A_2") (pintype "unspecified"))
      (node (ref "LED95") (pin "2") (pinfunction "A_2") (pintype "unspecified"))
      (node (ref "LED96") (pin "2") (pinfunction "A_2") (pintype "unspecified"))
      (node (ref "U3") (pin "13") (pinfunction "Y5_13") (pintype "unspecified"))
    )
    (net (code "9") (name "7") (class "Default")
      (node (ref "LED100") (pin "2") (pinfunction "A_2") (pintype "unspecified"))
      (node (ref "LED101") (pin "2") (pinfunction "A_2") (pintype "unspecified"))
      (node (ref "LED102") (pin "2") (pinfunction "A_2") (pintype "unspecified"))
      (node (ref "LED103") (pin "2") (pinfunction "A_2") (pintype "unspecified"))
      (node (ref "LED104") (pin "2") (pinfunction "A_2") (pintype "unspecified"))
      (node (ref "LED105") (pin "2") (pinfunction "A_2") (pintype "unspecified"))
      (node (ref "LED106") (pin "2") (pinfunction "A_2") (pintype "unspecified"))
      (node (ref "LED107") (pin "2") (pinfunction "A_2") (pintype "unspecified"))
      (node (ref "LED108") (pin "2") (pinfunction "A_2") (pintype "unspecified"))
      (node (ref "LED109") (pin "2") (pinfunction "A_2") (pintype "unspecified"))
      (node (ref "LED110") (pin "2") (pinfunction "A_2") (pintype "unspecified"))
      (node (ref "LED111") (pin "2") (pinfunction "A_2") (pintype "unspecified"))
      (node (ref "LED112") (pin "2") (pinfunction "A_2") (pintype "unspecified"))
      (node (ref "LED97") (pin "2") (pinfunction "A_2") (pintype "unspecified"))
      (node (ref "LED98") (pin "2") (pinfunction "A_2") (pintype "unspecified"))
      (node (ref "LED99") (pin "2") (pinfunction "A_2") (pintype "unspecified"))
      (node (ref "U3") (pin "12") (pinfunction "Y6_12") (pintype "unspecified"))
    )
    (net (code "10") (name "8") (class "Default")
      (node (ref "LED113") (pin "2") (pinfunction "A_2") (pintype "unspecified"))
      (node (ref "LED114") (pin "2") (pinfunction "A_2") (pintype "unspecified"))
      (node (ref "LED115") (pin "2") (pinfunction "A_2") (pintype "unspecified"))
      (node (ref "LED116") (pin "2") (pinfunction "A_2") (pintype "unspecified"))
      (node (ref "LED117") (pin "2") (pinfunction "A_2") (pintype "unspecified"))
      (node (ref "LED118") (pin "2") (pinfunction "A_2") (pintype "unspecified"))
      (node (ref "LED119") (pin "2") (pinfunction "A_2") (pintype "unspecified"))
      (node (ref "LED120") (pin "2") (pinfunction "A_2") (pintype "unspecified"))
      (node (ref "LED121") (pin "2") (pinfunction "A_2") (pintype "unspecified"))
      (node (ref "LED122") (pin "2") (pinfunction "A_2") (pintype "unspecified"))
      (node (ref "LED123") (pin "2") (pinfunction "A_2") (pintype "unspecified"))
      (node (ref "LED124") (pin "2") (pinfunction "A_2") (pintype "unspecified"))
      (node (ref "LED125") (pin "2") (pinfunction "A_2") (pintype "unspecified"))
      (node (ref "LED126") (pin "2") (pinfunction "A_2") (pintype "unspecified"))
      (node (ref "LED127") (pin "2") (pinfunction "A_2") (pintype "unspecified"))
      (node (ref "LED128") (pin "2") (pinfunction "A_2") (pintype "unspecified"))
      (node (ref "U3") (pin "11") (pinfunction "Y7_11") (pintype "unspecified"))
    )
    (net (code "11") (name "9") (class "Default")
      (node (ref "LED129") (pin "2") (pinfunction "A_2") (pintype "unspecified"))
      (node (ref "LED130") (pin "2") (pinfunction "A_2") (pintype "unspecified"))
      (node (ref "LED131") (pin "2") (pinfunction "A_2") (pintype "unspecified"))
      (node (ref "LED132") (pin "2") (pinfunction "A_2") (pintype "unspecified"))
      (node (ref "LED133") (pin "2") (pinfunction "A_2") (pintype "unspecified"))
      (node (ref "LED134") (pin "2") (pinfunction "A_2") (pintype "unspecified"))
      (node (ref "LED135") (pin "2") (pinfunction "A_2") (pintype "unspecified"))
      (node (ref "LED136") (pin "2") (pinfunction "A_2") (pintype "unspecified"))
      (node (ref "LED137") (pin "2") (pinfunction "A_2") (pintype "unspecified"))
      (node (ref "LED138") (pin "2") (pinfunction "A_2") (pintype "unspecified"))
      (node (ref "LED139") (pin "2") (pinfunction "A_2") (pintype "unspecified"))
      (node (ref "LED140") (pin "2") (pinfunction "A_2") (pintype "unspecified"))
      (node (ref "LED141") (pin "2") (pinfunction "A_2") (pintype "unspecified"))
      (node (ref "LED142") (pin "2") (pinfunction "A_2") (pintype "unspecified"))
      (node (ref "LED143") (pin "2") (pinfunction "A_2") (pintype "unspecified"))
      (node (ref "LED144") (pin "2") (pinfunction "A_2") (pintype "unspecified"))
      (node (ref "U5") (pin "18") (pinfunction "Y0_18") (pintype "unspecified"))
    )
    (net (code "12") (name "10") (class "Default")
      (node (ref "LED145") (pin "2") (pinfunction "A_2") (pintype "unspecified"))
      (node (ref "LED146") (pin "2") (pinfunction "A_2") (pintype "unspecified"))
      (node (ref "LED147") (pin "2") (pinfunction "A_2") (pintype "unspecified"))
      (node (ref "LED148") (pin "2") (pinfunction "A_2") (pintype "unspecified"))
      (node (ref "LED149") (pin "2") (pinfunction "A_2") (pintype "unspecified"))
      (node (ref "LED150") (pin "2") (pinfunction "A_2") (pintype "unspecified"))
      (node (ref "LED151") (pin "2") (pinfunction "A_2") (pintype "unspecified"))
      (node (ref "LED152") (pin "2") (pinfunction "A_2") (pintype "unspecified"))
      (node (ref "LED153") (pin "2") (pinfunction "A_2") (pintype "unspecified"))
      (node (ref "LED154") (pin "2") (pinfunction "A_2") (pintype "unspecified"))
      (node (ref "LED155") (pin "2") (pinfunction "A_2") (pintype "unspecified"))
      (node (ref "LED156") (pin "2") (pinfunction "A_2") (pintype "unspecified"))
      (node (ref "LED157") (pin "2") (pinfunction "A_2") (pintype "unspecified"))
      (node (ref "LED158") (pin "2") (pinfunction "A_2") (pintype "unspecified"))
      (node (ref "LED159") (pin "2") (pinfunction "A_2") (pintype "unspecified"))
      (node (ref "LED160") (pin "2") (pinfunction "A_2") (pintype "unspecified"))
      (node (ref "U5") (pin "17") (pinfunction "Y1_17") (pintype "unspecified"))
    )
    (net (code "13") (name "11") (class "Default")
      (node (ref "LED161") (pin "2") (pinfunction "A_2") (pintype "unspecified"))
      (node (ref "LED162") (pin "2") (pinfunction "A_2") (pintype "unspecified"))
      (node (ref "LED163") (pin "2") (pinfunction "A_2") (pintype "unspecified"))
      (node (ref "LED164") (pin "2") (pinfunction "A_2") (pintype "unspecified"))
      (node (ref "LED165") (pin "2") (pinfunction "A_2") (pintype "unspecified"))
      (node (ref "LED166") (pin "2") (pinfunction "A_2") (pintype "unspecified"))
      (node (ref "LED167") (pin "2") (pinfunction "A_2") (pintype "unspecified"))
      (node (ref "LED168") (pin "2") (pinfunction "A_2") (pintype "unspecified"))
      (node (ref "LED169") (pin "2") (pinfunction "A_2") (pintype "unspecified"))
      (node (ref "LED170") (pin "2") (pinfunction "A_2") (pintype "unspecified"))
      (node (ref "LED171") (pin "2") (pinfunction "A_2") (pintype "unspecified"))
      (node (ref "LED172") (pin "2") (pinfunction "A_2") (pintype "unspecified"))
      (node (ref "LED173") (pin "2") (pinfunction "A_2") (pintype "unspecified"))
      (node (ref "LED174") (pin "2") (pinfunction "A_2") (pintype "unspecified"))
      (node (ref "LED175") (pin "2") (pinfunction "A_2") (pintype "unspecified"))
      (node (ref "LED176") (pin "2") (pinfunction "A_2") (pintype "unspecified"))
      (node (ref "U5") (pin "16") (pinfunction "Y2_16") (pintype "unspecified"))
    )
    (net (code "14") (name "12") (class "Default")
      (node (ref "LED177") (pin "2") (pinfunction "A_2") (pintype "unspecified"))
      (node (ref "LED178") (pin "2") (pinfunction "A_2") (pintype "unspecified"))
      (node (ref "LED179") (pin "2") (pinfunction "A_2") (pintype "unspecified"))
      (node (ref "LED180") (pin "2") (pinfunction "A_2") (pintype "unspecified"))
      (node (ref "LED181") (pin "2") (pinfunction "A_2") (pintype "unspecified"))
      (node (ref "LED182") (pin "2") (pinfunction "A_2") (pintype "unspecified"))
      (node (ref "LED183") (pin "2") (pinfunction "A_2") (pintype "unspecified"))
      (node (ref "LED184") (pin "2") (pinfunction "A_2") (pintype "unspecified"))
      (node (ref "LED185") (pin "2") (pinfunction "A_2") (pintype "unspecified"))
      (node (ref "LED186") (pin "2") (pinfunction "A_2") (pintype "unspecified"))
      (node (ref "LED187") (pin "2") (pinfunction "A_2") (pintype "unspecified"))
      (node (ref "LED188") (pin "2") (pinfunction "A_2") (pintype "unspecified"))
      (node (ref "LED189") (pin "2") (pinfunction "A_2") (pintype "unspecified"))
      (node (ref "LED190") (pin "2") (pinfunction "A_2") (pintype "unspecified"))
      (node (ref "LED191") (pin "2") (pinfunction "A_2") (pintype "unspecified"))
      (node (ref "LED192") (pin "2") (pinfunction "A_2") (pintype "unspecified"))
      (node (ref "U5") (pin "15") (pinfunction "Y3_15") (pintype "unspecified"))
    )
    (net (code "15") (name "13") (class "Default")
      (node (ref "LED193") (pin "2") (pinfunction "A_2") (pintype "unspecified"))
      (node (ref "LED194") (pin "2") (pinfunction "A_2") (pintype "unspecified"))
      (node (ref "LED195") (pin "2") (pinfunction "A_2") (pintype "unspecified"))
      (node (ref "LED196") (pin "2") (pinfunction "A_2") (pintype "unspecified"))
      (node (ref "LED197") (pin "2") (pinfunction "A_2") (pintype "unspecified"))
      (node (ref "LED198") (pin "2") (pinfunction "A_2") (pintype "unspecified"))
      (node (ref "LED199") (pin "2") (pinfunction "A_2") (pintype "unspecified"))
      (node (ref "LED200") (pin "2") (pinfunction "A_2") (pintype "unspecified"))
      (node (ref "LED201") (pin "2") (pinfunction "A_2") (pintype "unspecified"))
      (node (ref "LED202") (pin "2") (pinfunction "A_2") (pintype "unspecified"))
      (node (ref "LED203") (pin "2") (pinfunction "A_2") (pintype "unspecified"))
      (node (ref "LED204") (pin "2") (pinfunction "A_2") (pintype "unspecified"))
      (node (ref "LED205") (pin "2") (pinfunction "A_2") (pintype "unspecified"))
      (node (ref "LED206") (pin "2") (pinfunction "A_2") (pintype "unspecified"))
      (node (ref "LED207") (pin "2") (pinfunction "A_2") (pintype "unspecified"))
      (node (ref "LED208") (pin "2") (pinfunction "A_2") (pintype "unspecified"))
      (node (ref "U5") (pin "14") (pinfunction "Y4_14") (pintype "unspecified"))
    )
    (net (code "16") (name "14") (class "Default")
      (node (ref "LED209") (pin "2") (pinfunction "A_2") (pintype "unspecified"))
      (node (ref "LED210") (pin "2") (pinfunction "A_2") (pintype "unspecified"))
      (node (ref "LED211") (pin "2") (pinfunction "A_2") (pintype "unspecified"))
      (node (ref "LED212") (pin "2") (pinfunction "A_2") (pintype "unspecified"))
      (node (ref "LED213") (pin "2") (pinfunction "A_2") (pintype "unspecified"))
      (node (ref "LED214") (pin "2") (pinfunction "A_2") (pintype "unspecified"))
      (node (ref "LED215") (pin "2") (pinfunction "A_2") (pintype "unspecified"))
      (node (ref "LED216") (pin "2") (pinfunction "A_2") (pintype "unspecified"))
      (node (ref "LED217") (pin "2") (pinfunction "A_2") (pintype "unspecified"))
      (node (ref "LED218") (pin "2") (pinfunction "A_2") (pintype "unspecified"))
      (node (ref "LED219") (pin "2") (pinfunction "A_2") (pintype "unspecified"))
      (node (ref "LED220") (pin "2") (pinfunction "A_2") (pintype "unspecified"))
      (node (ref "LED221") (pin "2") (pinfunction "A_2") (pintype "unspecified"))
      (node (ref "LED222") (pin "2") (pinfunction "A_2") (pintype "unspecified"))
      (node (ref "LED223") (pin "2") (pinfunction "A_2") (pintype "unspecified"))
      (node (ref "LED224") (pin "2") (pinfunction "A_2") (pintype "unspecified"))
      (node (ref "U5") (pin "13") (pinfunction "Y5_13") (pintype "unspecified"))
    )
    (net (code "17") (name "15") (class "Default")
      (node (ref "LED225") (pin "2") (pinfunction "A_2") (pintype "unspecified"))
      (node (ref "LED226") (pin "2") (pinfunction "A_2") (pintype "unspecified"))
      (node (ref "LED227") (pin "2") (pinfunction "A_2") (pintype "unspecified"))
      (node (ref "LED228") (pin "2") (pinfunction "A_2") (pintype "unspecified"))
      (node (ref "LED229") (pin "2") (pinfunction "A_2") (pintype "unspecified"))
      (node (ref "LED230") (pin "2") (pinfunction "A_2") (pintype "unspecified"))
      (node (ref "LED231") (pin "2") (pinfunction "A_2") (pintype "unspecified"))
      (node (ref "LED232") (pin "2") (pinfunction "A_2") (pintype "unspecified"))
      (node (ref "LED233") (pin "2") (pinfunction "A_2") (pintype "unspecified"))
      (node (ref "LED234") (pin "2") (pinfunction "A_2") (pintype "unspecified"))
      (node (ref "LED235") (pin "2") (pinfunction "A_2") (pintype "unspecified"))
      (node (ref "LED236") (pin "2") (pinfunction "A_2") (pintype "unspecified"))
      (node (ref "LED237") (pin "2") (pinfunction "A_2") (pintype "unspecified"))
      (node (ref "LED238") (pin "2") (pinfunction "A_2") (pintype "unspecified"))
      (node (ref "LED239") (pin "2") (pinfunction "A_2") (pintype "unspecified"))
      (node (ref "LED240") (pin "2") (pinfunction "A_2") (pintype "unspecified"))
      (node (ref "U5") (pin "12") (pinfunction "Y6_12") (pintype "unspecified"))
    )
    (net (code "18") (name "16") (class "Default")
      (node (ref "LED241") (pin "2") (pinfunction "A_2") (pintype "unspecified"))
      (node (ref "LED242") (pin "2") (pinfunction "A_2") (pintype "unspecified"))
      (node (ref "LED243") (pin "2") (pinfunction "A_2") (pintype "unspecified"))
      (node (ref "LED244") (pin "2") (pinfunction "A_2") (pintype "unspecified"))
      (node (ref "LED245") (pin "2") (pinfunction "A_2") (pintype "unspecified"))
      (node (ref "LED246") (pin "2") (pinfunction "A_2") (pintype "unspecified"))
      (node (ref "LED247") (pin "2") (pinfunction "A_2") (pintype "unspecified"))
      (node (ref "LED248") (pin "2") (pinfunction "A_2") (pintype "unspecified"))
      (node (ref "LED249") (pin "2") (pinfunction "A_2") (pintype "unspecified"))
      (node (ref "LED250") (pin "2") (pinfunction "A_2") (pintype "unspecified"))
      (node (ref "LED251") (pin "2") (pinfunction "A_2") (pintype "unspecified"))
      (node (ref "LED252") (pin "2") (pinfunction "A_2") (pintype "unspecified"))
      (node (ref "LED253") (pin "2") (pinfunction "A_2") (pintype "unspecified"))
      (node (ref "LED254") (pin "2") (pinfunction "A_2") (pintype "unspecified"))
      (node (ref "LED255") (pin "2") (pinfunction "A_2") (pintype "unspecified"))
      (node (ref "LED256") (pin "2") (pinfunction "A_2") (pintype "unspecified"))
      (node (ref "U5") (pin "11") (pinfunction "Y7_11") (pintype "unspecified"))
    )
    (net (code "19") (name "A") (class "Default")
      (node (ref "LED1") (pin "1") (pinfunction "K_1") (pintype "unspecified"))
      (node (ref "LED113") (pin "1") (pinfunction "K_1") (pintype "unspecified"))
      (node (ref "LED129") (pin "1") (pinfunction "K_1") (pintype "unspecified"))
      (node (ref "LED145") (pin "1") (pinfunction "K_1") (pintype "unspecified"))
      (node (ref "LED161") (pin "1") (pinfunction "K_1") (pintype "unspecified"))
      (node (ref "LED17") (pin "1") (pinfunction "K_1") (pintype "unspecified"))
      (node (ref "LED177") (pin "1") (pinfunction "K_1") (pintype "unspecified"))
      (node (ref "LED193") (pin "1") (pinfunction "K_1") (pintype "unspecified"))
      (node (ref "LED209") (pin "1") (pinfunction "K_1") (pintype "unspecified"))
      (node (ref "LED225") (pin "1") (pinfunction "K_1") (pintype "unspecified"))
      (node (ref "LED241") (pin "1") (pinfunction "K_1") (pintype "unspecified"))
      (node (ref "LED33") (pin "1") (pinfunction "K_1") (pintype "unspecified"))
      (node (ref "LED49") (pin "1") (pinfunction "K_1") (pintype "unspecified"))
      (node (ref "LED65") (pin "1") (pinfunction "K_1") (pintype "unspecified"))
      (node (ref "LED81") (pin "1") (pinfunction "K_1") (pintype "unspecified"))
      (node (ref "LED97") (pin "1") (pinfunction "K_1") (pintype "unspecified"))
      (node (ref "U23") (pin "2") (pinfunction "2_2") (pintype "unspecified"))
    )
    (net (code "20") (name "B") (class "Default")
      (node (ref "LED114") (pin "1") (pinfunction "K_1") (pintype "unspecified"))
      (node (ref "LED130") (pin "1") (pinfunction "K_1") (pintype "unspecified"))
      (node (ref "LED146") (pin "1") (pinfunction "K_1") (pintype "unspecified"))
      (node (ref "LED162") (pin "1") (pinfunction "K_1") (pintype "unspecified"))
      (node (ref "LED178") (pin "1") (pinfunction "K_1") (pintype "unspecified"))
      (node (ref "LED18") (pin "1") (pinfunction "K_1") (pintype "unspecified"))
      (node (ref "LED194") (pin "1") (pinfunction "K_1") (pintype "unspecified"))
      (node (ref "LED2") (pin "1") (pinfunction "K_1") (pintype "unspecified"))
      (node (ref "LED210") (pin "1") (pinfunction "K_1") (pintype "unspecified"))
      (node (ref "LED226") (pin "1") (pinfunction "K_1") (pintype "unspecified"))
      (node (ref "LED242") (pin "1") (pinfunction "K_1") (pintype "unspecified"))
      (node (ref "LED34") (pin "1") (pinfunction "K_1") (pintype "unspecified"))
      (node (ref "LED50") (pin "1") (pinfunction "K_1") (pintype "unspecified"))
      (node (ref "LED66") (pin "1") (pinfunction "K_1") (pintype "unspecified"))
      (node (ref "LED82") (pin "1") (pinfunction "K_1") (pintype "unspecified"))
      (node (ref "LED98") (pin "1") (pinfunction "K_1") (pintype "unspecified"))
      (node (ref "U22") (pin "2") (pinfunction "2_2") (pintype "unspecified"))
    )
    (net (code "21") (name "C") (class "Default")
      (node (ref "LED115") (pin "1") (pinfunction "K_1") (pintype "unspecified"))
      (node (ref "LED131") (pin "1") (pinfunction "K_1") (pintype "unspecified"))
      (node (ref "LED147") (pin "1") (pinfunction "K_1") (pintype "unspecified"))
      (node (ref "LED163") (pin "1") (pinfunction "K_1") (pintype "unspecified"))
      (node (ref "LED179") (pin "1") (pinfunction "K_1") (pintype "unspecified"))
      (node (ref "LED19") (pin "1") (pinfunction "K_1") (pintype "unspecified"))
      (node (ref "LED195") (pin "1") (pinfunction "K_1") (pintype "unspecified"))
      (node (ref "LED211") (pin "1") (pinfunction "K_1") (pintype "unspecified"))
      (node (ref "LED227") (pin "1") (pinfunction "K_1") (pintype "unspecified"))
      (node (ref "LED243") (pin "1") (pinfunction "K_1") (pintype "unspecified"))
      (node (ref "LED3") (pin "1") (pinfunction "K_1") (pintype "unspecified"))
      (node (ref "LED35") (pin "1") (pinfunction "K_1") (pintype "unspecified"))
      (node (ref "LED51") (pin "1") (pinfunction "K_1") (pintype "unspecified"))
      (node (ref "LED67") (pin "1") (pinfunction "K_1") (pintype "unspecified"))
      (node (ref "LED83") (pin "1") (pinfunction "K_1") (pintype "unspecified"))
      (node (ref "LED99") (pin "1") (pinfunction "K_1") (pintype "unspecified"))
      (node (ref "U21") (pin "2") (pinfunction "2_2") (pintype "unspecified"))
    )
    (net (code "22") (name "D") (class "Default")
      (node (ref "LED100") (pin "1") (pinfunction "K_1") (pintype "unspecified"))
      (node (ref "LED116") (pin "1") (pinfunction "K_1") (pintype "unspecified"))
      (node (ref "LED132") (pin "1") (pinfunction "K_1") (pintype "unspecified"))
      (node (ref "LED148") (pin "1") (pinfunction "K_1") (pintype "unspecified"))
      (node (ref "LED164") (pin "1") (pinfunction "K_1") (pintype "unspecified"))
      (node (ref "LED180") (pin "1") (pinfunction "K_1") (pintype "unspecified"))
      (node (ref "LED196") (pin "1") (pinfunction "K_1") (pintype "unspecified"))
      (node (ref "LED20") (pin "1") (pinfunction "K_1") (pintype "unspecified"))
      (node (ref "LED212") (pin "1") (pinfunction "K_1") (pintype "unspecified"))
      (node (ref "LED228") (pin "1") (pinfunction "K_1") (pintype "unspecified"))
      (node (ref "LED244") (pin "1") (pinfunction "K_1") (pintype "unspecified"))
      (node (ref "LED36") (pin "1") (pinfunction "K_1") (pintype "unspecified"))
      (node (ref "LED4") (pin "1") (pinfunction "K_1") (pintype "unspecified"))
      (node (ref "LED52") (pin "1") (pinfunction "K_1") (pintype "unspecified"))
      (node (ref "LED68") (pin "1") (pinfunction "K_1") (pintype "unspecified"))
      (node (ref "LED84") (pin "1") (pinfunction "K_1") (pintype "unspecified"))
      (node (ref "U20") (pin "2") (pinfunction "2_2") (pintype "unspecified"))
    )
    (net (code "23") (name "E") (class "Default")
      (node (ref "LED101") (pin "1") (pinfunction "K_1") (pintype "unspecified"))
      (node (ref "LED117") (pin "1") (pinfunction "K_1") (pintype "unspecified"))
      (node (ref "LED133") (pin "1") (pinfunction "K_1") (pintype "unspecified"))
      (node (ref "LED149") (pin "1") (pinfunction "K_1") (pintype "unspecified"))
      (node (ref "LED165") (pin "1") (pinfunction "K_1") (pintype "unspecified"))
      (node (ref "LED181") (pin "1") (pinfunction "K_1") (pintype "unspecified"))
      (node (ref "LED197") (pin "1") (pinfunction "K_1") (pintype "unspecified"))
      (node (ref "LED21") (pin "1") (pinfunction "K_1") (pintype "unspecified"))
      (node (ref "LED213") (pin "1") (pinfunction "K_1") (pintype "unspecified"))
      (node (ref "LED229") (pin "1") (pinfunction "K_1") (pintype "unspecified"))
      (node (ref "LED245") (pin "1") (pinfunction "K_1") (pintype "unspecified"))
      (node (ref "LED37") (pin "1") (pinfunction "K_1") (pintype "unspecified"))
      (node (ref "LED5") (pin "1") (pinfunction "K_1") (pintype "unspecified"))
      (node (ref "LED53") (pin "1") (pinfunction "K_1") (pintype "unspecified"))
      (node (ref "LED69") (pin "1") (pinfunction "K_1") (pintype "unspecified"))
      (node (ref "LED85") (pin "1") (pinfunction "K_1") (pintype "unspecified"))
      (node (ref "U19") (pin "2") (pinfunction "2_2") (pintype "unspecified"))
    )
    (net (code "24") (name "F") (class "Default")
      (node (ref "LED102") (pin "1") (pinfunction "K_1") (pintype "unspecified"))
      (node (ref "LED118") (pin "1") (pinfunction "K_1") (pintype "unspecified"))
      (node (ref "LED134") (pin "1") (pinfunction "K_1") (pintype "unspecified"))
      (node (ref "LED150") (pin "1") (pinfunction "K_1") (pintype "unspecified"))
      (node (ref "LED166") (pin "1") (pinfunction "K_1") (pintype "unspecified"))
      (node (ref "LED182") (pin "1") (pinfunction "K_1") (pintype "unspecified"))
      (node (ref "LED198") (pin "1") (pinfunction "K_1") (pintype "unspecified"))
      (node (ref "LED214") (pin "1") (pinfunction "K_1") (pintype "unspecified"))
      (node (ref "LED22") (pin "1") (pinfunction "K_1") (pintype "unspecified"))
      (node (ref "LED230") (pin "1") (pinfunction "K_1") (pintype "unspecified"))
      (node (ref "LED246") (pin "1") (pinfunction "K_1") (pintype "unspecified"))
      (node (ref "LED38") (pin "1") (pinfunction "K_1") (pintype "unspecified"))
      (node (ref "LED54") (pin "1") (pinfunction "K_1") (pintype "unspecified"))
      (node (ref "LED6") (pin "1") (pinfunction "K_1") (pintype "unspecified"))
      (node (ref "LED70") (pin "1") (pinfunction "K_1") (pintype "unspecified"))
      (node (ref "LED86") (pin "1") (pinfunction "K_1") (pintype "unspecified"))
      (node (ref "U18") (pin "2") (pinfunction "2_2") (pintype "unspecified"))
    )
    (net (code "25") (name "G") (class "Default")
      (node (ref "LED103") (pin "1") (pinfunction "K_1") (pintype "unspecified"))
      (node (ref "LED119") (pin "1") (pinfunction "K_1") (pintype "unspecified"))
      (node (ref "LED135") (pin "1") (pinfunction "K_1") (pintype "unspecified"))
      (node (ref "LED151") (pin "1") (pinfunction "K_1") (pintype "unspecified"))
      (node (ref "LED167") (pin "1") (pinfunction "K_1") (pintype "unspecified"))
      (node (ref "LED183") (pin "1") (pinfunction "K_1") (pintype "unspecified"))
      (node (ref "LED199") (pin "1") (pinfunction "K_1") (pintype "unspecified"))
      (node (ref "LED215") (pin "1") (pinfunction "K_1") (pintype "unspecified"))
      (node (ref "LED23") (pin "1") (pinfunction "K_1") (pintype "unspecified"))
      (node (ref "LED231") (pin "1") (pinfunction "K_1") (pintype "unspecified"))
      (node (ref "LED247") (pin "1") (pinfunction "K_1") (pintype "unspecified"))
      (node (ref "LED39") (pin "1") (pinfunction "K_1") (pintype "unspecified"))
      (node (ref "LED55") (pin "1") (pinfunction "K_1") (pintype "unspecified"))
      (node (ref "LED7") (pin "1") (pinfunction "K_1") (pintype "unspecified"))
      (node (ref "LED71") (pin "1") (pinfunction "K_1") (pintype "unspecified"))
      (node (ref "LED87") (pin "1") (pinfunction "K_1") (pintype "unspecified"))
      (node (ref "U17") (pin "2") (pinfunction "2_2") (pintype "unspecified"))
    )
    (net (code "26") (name "GND") (class "Default")
      (node (ref "C1") (pin "1") (pinfunction "1_1") (pintype "unspecified"))
      (node (ref "C2") (pin "1") (pinfunction "1_1") (pintype "unspecified"))
      (node (ref "C3") (pin "1") (pinfunction "1_1") (pintype "unspecified"))
      (node (ref "C4") (pin "1") (pinfunction "1_1") (pintype "unspecified"))
      (node (ref "C5") (pin "2") (pinfunction "2_2") (pintype "input"))
      (node (ref "C6") (pin "2") (pinfunction "2_2") (pintype "unspecified"))
      (node (ref "J3") (pin "1") (pinfunction "1_1") (pintype "unspecified"))
      (node (ref "Q17") (pin "1") (pinfunction "SOURCE_1") (pintype "unspecified"))
      (node (ref "Q18") (pin "3") (pinfunction "S_3") (pintype "unspecified"))
      (node (ref "Q19") (pin "3") (pinfunction "S_3") (pintype "unspecified"))
      (node (ref "Q20") (pin "3") (pinfunction "S_3") (pintype "unspecified"))
      (node (ref "Q21") (pin "3") (pinfunction "S_3") (pintype "unspecified"))
      (node (ref "Q22") (pin "3") (pinfunction "S_3") (pintype "unspecified"))
      (node (ref "Q23") (pin "3") (pinfunction "S_3") (pintype "unspecified"))
      (node (ref "Q24") (pin "3") (pinfunction "S_3") (pintype "unspecified"))
      (node (ref "Q25") (pin "3") (pinfunction "S_3") (pintype "unspecified"))
      (node (ref "Q26") (pin "3") (pinfunction "S_3") (pintype "unspecified"))
      (node (ref "Q27") (pin "3") (pinfunction "S_3") (pintype "unspecified"))
      (node (ref "Q28") (pin "3") (pinfunction "S_3") (pintype "unspecified"))
      (node (ref "Q29") (pin "3") (pinfunction "S_3") (pintype "unspecified"))
      (node (ref "Q30") (pin "3") (pinfunction "S_3") (pintype "unspecified"))
      (node (ref "Q31") (pin "3") (pinfunction "S_3") (pintype "unspecified"))
      (node (ref "Q32") (pin "3") (pinfunction "S_3") (pintype "unspecified"))
      (node (ref "Q33") (pin "3") (pinfunction "S_3") (pintype "unspecified"))
      (node (ref "R17") (pin "1") (pinfunction "1_1") (pintype "unspecified"))
      (node (ref "R19") (pin "1") (pinfunction "1_1") (pintype "unspecified"))
      (node (ref "R24") (pin "2") (pinfunction "2_2") (pintype "unspecified"))
      (node (ref "R25") (pin "2") (pinfunction "2_2") (pintype "unspecified"))
      (node (ref "R26") (pin "2") (pinfunction "2_2") (pintype "unspecified"))
      (node (ref "R27") (pin "2") (pinfunction "2_2") (pintype "unspecified"))
      (node (ref "R28") (pin "2") (pinfunction "2_2") (pintype "unspecified"))
      (node (ref "R29") (pin "2") (pinfunction "2_2") (pintype "unspecified"))
      (node (ref "R30") (pin "2") (pinfunction "2_2") (pintype "unspecified"))
      (node (ref "R31") (pin "2") (pinfunction "2_2") (pintype "unspecified"))
      (node (ref "R32") (pin "2") (pinfunction "2_2") (pintype "unspecified"))
      (node (ref "R33") (pin "2") (pinfunction "2_2") (pintype "unspecified"))
      (node (ref "R34") (pin "2") (pinfunction "2_2") (pintype "unspecified"))
      (node (ref "R35") (pin "2") (pinfunction "2_2") (pintype "unspecified"))
      (node (ref "R36") (pin "2") (pinfunction "2_2") (pintype "unspecified"))
      (node (ref "R37") (pin "2") (pinfunction "2_2") (pintype "unspecified"))
      (node (ref "U1") (pin "12") (pinfunction "GND_12") (pintype "unspecified"))
      (node (ref "U1") (pin "18") (pinfunction "CS1_18") (pintype "unspecified"))
      (node (ref "U1") (pin "19") (pinfunction "CS2_19") (pintype "unspecified"))
      (node (ref "U2") (pin "8") (pinfunction "GND_8") (pintype "unspecified"))
      (node (ref "U3") (pin "10") (pinfunction "GND_10") (pintype "unspecified"))
      (node (ref "U3") (pin "19") (pinfunction "OE2#_19") (pintype "unspecified"))
      (node (ref "U3") (pin "5") (pinfunction "A3_5") (pintype "unspecified"))
      (node (ref "U4") (pin "8") (pinfunction "GND_8") (pintype "unspecified"))
      (node (ref "U5") (pin "10") (pinfunction "GND_10") (pintype "unspecified"))
      (node (ref "U5") (pin "19") (pinfunction "OE2#_19") (pintype "unspecified"))
      (node (ref "U5") (pin "5") (pinfunction "A3_5") (pintype "unspecified"))
      (node (ref "U6") (pin "14") (pinfunction "GND_14") (pintype "unspecified"))
      (node (ref "U6") (pin "15") (pinfunction "I/O3_15") (pintype "unspecified"))
      (node (ref "U7") (pin "2") (pinfunction "GND_2") (pintype "unspecified"))
      (node (ref "U7") (pin "3") (pinfunction "OUT_3") (pintype "unspecified"))
    )
    (net (code "27") (name "H") (class "Default")
      (node (ref "LED104") (pin "1") (pinfunction "K_1") (pintype "unspecified"))
      (node (ref "LED120") (pin "1") (pinfunction "K_1") (pintype "unspecified"))
      (node (ref "LED136") (pin "1") (pinfunction "K_1") (pintype "unspecified"))
      (node (ref "LED152") (pin "1") (pinfunction "K_1") (pintype "unspecified"))
      (node (ref "LED168") (pin "1") (pinfunction "K_1") (pintype "unspecified"))
      (node (ref "LED184") (pin "1") (pinfunction "K_1") (pintype "unspecified"))
      (node (ref "LED200") (pin "1") (pinfunction "K_1") (pintype "unspecified"))
      (node (ref "LED216") (pin "1") (pinfunction "K_1") (pintype "unspecified"))
      (node (ref "LED232") (pin "1") (pinfunction "K_1") (pintype "unspecified"))
      (node (ref "LED24") (pin "1") (pinfunction "K_1") (pintype "unspecified"))
      (node (ref "LED248") (pin "1") (pinfunction "K_1") (pintype "unspecified"))
      (node (ref "LED40") (pin "1") (pinfunction "K_1") (pintype "unspecified"))
      (node (ref "LED56") (pin "1") (pinfunction "K_1") (pintype "unspecified"))
      (node (ref "LED72") (pin "1") (pinfunction "K_1") (pintype "unspecified"))
      (node (ref "LED8") (pin "1") (pinfunction "K_1") (pintype "unspecified"))
      (node (ref "LED88") (pin "1") (pinfunction "K_1") (pintype "unspecified"))
      (node (ref "U16") (pin "2") (pinfunction "2_2") (pintype "unspecified"))
    )
    (net (code "28") (name "I") (class "Default")
      (node (ref "LED105") (pin "1") (pinfunction "K_1") (pintype "unspecified"))
      (node (ref "LED121") (pin "1") (pinfunction "K_1") (pintype "unspecified"))
      (node (ref "LED137") (pin "1") (pinfunction "K_1") (pintype "unspecified"))
      (node (ref "LED153") (pin "1") (pinfunction "K_1") (pintype "unspecified"))
      (node (ref "LED169") (pin "1") (pinfunction "K_1") (pintype "unspecified"))
      (node (ref "LED185") (pin "1") (pinfunction "K_1") (pintype "unspecified"))
      (node (ref "LED201") (pin "1") (pinfunction "K_1") (pintype "unspecified"))
      (node (ref "LED217") (pin "1") (pinfunction "K_1") (pintype "unspecified"))
      (node (ref "LED233") (pin "1") (pinfunction "K_1") (pintype "unspecified"))
      (node (ref "LED249") (pin "1") (pinfunction "K_1") (pintype "unspecified"))
      (node (ref "LED25") (pin "1") (pinfunction "K_1") (pintype "unspecified"))
      (node (ref "LED41") (pin "1") (pinfunction "K_1") (pintype "unspecified"))
      (node (ref "LED57") (pin "1") (pinfunction "K_1") (pintype "unspecified"))
      (node (ref "LED73") (pin "1") (pinfunction "K_1") (pintype "unspecified"))
      (node (ref "LED89") (pin "1") (pinfunction "K_1") (pintype "unspecified"))
      (node (ref "LED9") (pin "1") (pinfunction "K_1") (pintype "unspecified"))
      (node (ref "U15") (pin "2") (pinfunction "2_2") (pintype "unspecified"))
    )
    (net (code "29") (name "J") (class "Default")
      (node (ref "LED10") (pin "1") (pinfunction "K_1") (pintype "unspecified"))
      (node (ref "LED106") (pin "1") (pinfunction "K_1") (pintype "unspecified"))
      (node (ref "LED122") (pin "1") (pinfunction "K_1") (pintype "unspecified"))
      (node (ref "LED138") (pin "1") (pinfunction "K_1") (pintype "unspecified"))
      (node (ref "LED154") (pin "1") (pinfunction "K_1") (pintype "unspecified"))
      (node (ref "LED170") (pin "1") (pinfunction "K_1") (pintype "unspecified"))
      (node (ref "LED186") (pin "1") (pinfunction "K_1") (pintype "unspecified"))
      (node (ref "LED202") (pin "1") (pinfunction "K_1") (pintype "unspecified"))
      (node (ref "LED218") (pin "1") (pinfunction "K_1") (pintype "unspecified"))
      (node (ref "LED234") (pin "1") (pinfunction "K_1") (pintype "unspecified"))
      (node (ref "LED250") (pin "1") (pinfunction "K_1") (pintype "unspecified"))
      (node (ref "LED26") (pin "1") (pinfunction "K_1") (pintype "unspecified"))
      (node (ref "LED42") (pin "1") (pinfunction "K_1") (pintype "unspecified"))
      (node (ref "LED58") (pin "1") (pinfunction "K_1") (pintype "unspecified"))
      (node (ref "LED74") (pin "1") (pinfunction "K_1") (pintype "unspecified"))
      (node (ref "LED90") (pin "1") (pinfunction "K_1") (pintype "unspecified"))
      (node (ref "U14") (pin "2") (pinfunction "2_2") (pintype "unspecified"))
    )
    (net (code "30") (name "K") (class "Default")
      (node (ref "LED107") (pin "1") (pinfunction "K_1") (pintype "unspecified"))
      (node (ref "LED11") (pin "1") (pinfunction "K_1") (pintype "unspecified"))
      (node (ref "LED123") (pin "1") (pinfunction "K_1") (pintype "unspecified"))
      (node (ref "LED139") (pin "1") (pinfunction "K_1") (pintype "unspecified"))
      (node (ref "LED155") (pin "1") (pinfunction "K_1") (pintype "unspecified"))
      (node (ref "LED171") (pin "1") (pinfunction "K_1") (pintype "unspecified"))
      (node (ref "LED187") (pin "1") (pinfunction "K_1") (pintype "unspecified"))
      (node (ref "LED203") (pin "1") (pinfunction "K_1") (pintype "unspecified"))
      (node (ref "LED219") (pin "1") (pinfunction "K_1") (pintype "unspecified"))
      (node (ref "LED235") (pin "1") (pinfunction "K_1") (pintype "unspecified"))
      (node (ref "LED251") (pin "1") (pinfunction "K_1") (pintype "unspecified"))
      (node (ref "LED27") (pin "1") (pinfunction "K_1") (pintype "unspecified"))
      (node (ref "LED43") (pin "1") (pinfunction "K_1") (pintype "unspecified"))
      (node (ref "LED59") (pin "1") (pinfunction "K_1") (pintype "unspecified"))
      (node (ref "LED75") (pin "1") (pinfunction "K_1") (pintype "unspecified"))
      (node (ref "LED91") (pin "1") (pinfunction "K_1") (pintype "unspecified"))
      (node (ref "U13") (pin "2") (pinfunction "2_2") (pintype "unspecified"))
    )
    (net (code "31") (name "L") (class "Default")
      (node (ref "LED108") (pin "1") (pinfunction "K_1") (pintype "unspecified"))
      (node (ref "LED12") (pin "1") (pinfunction "K_1") (pintype "unspecified"))
      (node (ref "LED124") (pin "1") (pinfunction "K_1") (pintype "unspecified"))
      (node (ref "LED140") (pin "1") (pinfunction "K_1") (pintype "unspecified"))
      (node (ref "LED156") (pin "1") (pinfunction "K_1") (pintype "unspecified"))
      (node (ref "LED172") (pin "1") (pinfunction "K_1") (pintype "unspecified"))
      (node (ref "LED188") (pin "1") (pinfunction "K_1") (pintype "unspecified"))
      (node (ref "LED204") (pin "1") (pinfunction "K_1") (pintype "unspecified"))
      (node (ref "LED220") (pin "1") (pinfunction "K_1") (pintype "unspecified"))
      (node (ref "LED236") (pin "1") (pinfunction "K_1") (pintype "unspecified"))
      (node (ref "LED252") (pin "1") (pinfunction "K_1") (pintype "unspecified"))
      (node (ref "LED28") (pin "1") (pinfunction "K_1") (pintype "unspecified"))
      (node (ref "LED44") (pin "1") (pinfunction "K_1") (pintype "unspecified"))
      (node (ref "LED60") (pin "1") (pinfunction "K_1") (pintype "unspecified"))
      (node (ref "LED76") (pin "1") (pinfunction "K_1") (pintype "unspecified"))
      (node (ref "LED92") (pin "1") (pinfunction "K_1") (pintype "unspecified"))
      (node (ref "U12") (pin "2") (pinfunction "2_2") (pintype "unspecified"))
    )
    (net (code "32") (name "M") (class "Default")
      (node (ref "LED109") (pin "1") (pinfunction "K_1") (pintype "unspecified"))
      (node (ref "LED125") (pin "1") (pinfunction "K_1") (pintype "unspecified"))
      (node (ref "LED13") (pin "1") (pinfunction "K_1") (pintype "unspecified"))
      (node (ref "LED141") (pin "1") (pinfunction "K_1") (pintype "unspecified"))
      (node (ref "LED157") (pin "1") (pinfunction "K_1") (pintype "unspecified"))
      (node (ref "LED173") (pin "1") (pinfunction "K_1") (pintype "unspecified"))
      (node (ref "LED189") (pin "1") (pinfunction "K_1") (pintype "unspecified"))
      (node (ref "LED205") (pin "1") (pinfunction "K_1") (pintype "unspecified"))
      (node (ref "LED221") (pin "1") (pinfunction "K_1") (pintype "unspecified"))
      (node (ref "LED237") (pin "1") (pinfunction "K_1") (pintype "unspecified"))
      (node (ref "LED253") (pin "1") (pinfunction "K_1") (pintype "unspecified"))
      (node (ref "LED29") (pin "1") (pinfunction "K_1") (pintype "unspecified"))
      (node (ref "LED45") (pin "1") (pinfunction "K_1") (pintype "unspecified"))
      (node (ref "LED61") (pin "1") (pinfunction "K_1") (pintype "unspecified"))
      (node (ref "LED77") (pin "1") (pinfunction "K_1") (pintype "unspecified"))
      (node (ref "LED93") (pin "1") (pinfunction "K_1") (pintype "unspecified"))
      (node (ref "U11") (pin "2") (pinfunction "2_2") (pintype "unspecified"))
    )
    (net (code "33") (name "N") (class "Default")
      (node (ref "LED110") (pin "1") (pinfunction "K_1") (pintype "unspecified"))
      (node (ref "LED126") (pin "1") (pinfunction "K_1") (pintype "unspecified"))
      (node (ref "LED14") (pin "1") (pinfunction "K_1") (pintype "unspecified"))
      (node (ref "LED142") (pin "1") (pinfunction "K_1") (pintype "unspecified"))
      (node (ref "LED158") (pin "1") (pinfunction "K_1") (pintype "unspecified"))
      (node (ref "LED174") (pin "1") (pinfunction "K_1") (pintype "unspecified"))
      (node (ref "LED190") (pin "1") (pinfunction "K_1") (pintype "unspecified"))
      (node (ref "LED206") (pin "1") (pinfunction "K_1") (pintype "unspecified"))
      (node (ref "LED222") (pin "1") (pinfunction "K_1") (pintype "unspecified"))
      (node (ref "LED238") (pin "1") (pinfunction "K_1") (pintype "unspecified"))
      (node (ref "LED254") (pin "1") (pinfunction "K_1") (pintype "unspecified"))
      (node (ref "LED30") (pin "1") (pinfunction "K_1") (pintype "unspecified"))
      (node (ref "LED46") (pin "1") (pinfunction "K_1") (pintype "unspecified"))
      (node (ref "LED62") (pin "1") (pinfunction "K_1") (pintype "unspecified"))
      (node (ref "LED78") (pin "1") (pinfunction "K_1") (pintype "unspecified"))
      (node (ref "LED94") (pin "1") (pinfunction "K_1") (pintype "unspecified"))
      (node (ref "U10") (pin "2") (pinfunction "2_2") (pintype "unspecified"))
    )
    (net (code "34") (name "Net-(C4-Pad2)") (class "Default")
      (node (ref "C4") (pin "2") (pinfunction "2_2") (pintype "unspecified"))
      (node (ref "R22") (pin "1") (pinfunction "1_1") (pintype "unspecified"))
      (node (ref "X1") (pin "2") (pinfunction "2_2") (pintype "unspecified"))
    )
    (net (code "35") (name "Net-(Q17-DRAIN)") (class "Default")
      (node (ref "Q17") (pin "3") (pinfunction "DRAIN_3") (pintype "unspecified"))
      (node (ref "R18") (pin "1") (pinfunction "1_1") (pintype "unspecified"))
      (node (ref "U3") (pin "1") (pinfunction "OE1#_1") (pintype "unspecified"))
    )
    (net (code "36") (name "Net-(Q17-GATE)") (class "Default")
      (node (ref "Q17") (pin "2") (pinfunction "GATE_2") (pintype "unspecified"))
      (node (ref "U4") (pin "15") (pinfunction "QA_15") (pintype "unspecified"))
      (node (ref "U5") (pin "1") (pinfunction "OE1#_1") (pintype "unspecified"))
      (node (ref "U6") (pin "10") (pinfunction "A0_10") (pintype "unspecified"))
    )
    (net (code "37") (name "Net-(Q18-D)") (class "Default")
      (node (ref "Q18") (pin "2") (pinfunction "D_2") (pintype "unspecified"))
      (node (ref "R16") (pin "2") (pinfunction "2_2") (pintype "unspecified"))
      (node (ref "U8") (pin "1") (pinfunction "1_1") (pintype "unspecified"))
    )
    (net (code "38") (name "Net-(Q18-G)") (class "Default")
      (node (ref "Q18") (pin "1") (pinfunction "G_1") (pintype "unspecified"))
      (node (ref "U1") (pin "17") (pinfunction "Y15_17") (pintype "unspecified"))
    )
    (net (code "39") (name "Net-(Q19-D)") (class "Default")
      (node (ref "Q19") (pin "2") (pinfunction "D_2") (pintype "unspecified"))
      (node (ref "R15") (pin "2") (pinfunction "2_2") (pintype "unspecified"))
      (node (ref "U9") (pin "1") (pinfunction "1_1") (pintype "unspecified"))
    )
    (net (code "40") (name "Net-(Q19-G)") (class "Default")
      (node (ref "Q19") (pin "1") (pinfunction "G_1") (pintype "unspecified"))
      (node (ref "U1") (pin "16") (pinfunction "Y14_16") (pintype "unspecified"))
    )
    (net (code "41") (name "Net-(Q20-D)") (class "Default")
      (node (ref "Q20") (pin "2") (pinfunction "D_2") (pintype "unspecified"))
      (node (ref "R14") (pin "2") (pinfunction "2_2") (pintype "unspecified"))
      (node (ref "U10") (pin "1") (pinfunction "1_1") (pintype "unspecified"))
    )
    (net (code "42") (name "Net-(Q20-G)") (class "Default")
      (node (ref "Q20") (pin "1") (pinfunction "G_1") (pintype "unspecified"))
      (node (ref "U1") (pin "15") (pinfunction "Y13_15") (pintype "unspecified"))
    )
    (net (code "43") (name "Net-(Q21-D)") (class "Default")
      (node (ref "Q21") (pin "2") (pinfunction "D_2") (pintype "unspecified"))
      (node (ref "R13") (pin "2") (pinfunction "2_2") (pintype "unspecified"))
      (node (ref "U11") (pin "1") (pinfunction "1_1") (pintype "unspecified"))
    )
    (net (code "44") (name "Net-(Q21-G)") (class "Default")
      (node (ref "Q21") (pin "1") (pinfunction "G_1") (pintype "unspecified"))
      (node (ref "U1") (pin "14") (pinfunction "Y12_14") (pintype "unspecified"))
    )
    (net (code "45") (name "Net-(Q22-D)") (class "Default")
      (node (ref "Q22") (pin "2") (pinfunction "D_2") (pintype "unspecified"))
      (node (ref "R12") (pin "2") (pinfunction "2_2") (pintype "unspecified"))
      (node (ref "U12") (pin "1") (pinfunction "1_1") (pintype "unspecified"))
    )
    (net (code "46") (name "Net-(Q22-G)") (class "Default")
      (node (ref "Q22") (pin "1") (pinfunction "G_1") (pintype "unspecified"))
      (node (ref "U1") (pin "13") (pinfunction "Y11_13") (pintype "unspecified"))
    )
    (net (code "47") (name "Net-(Q23-D)") (class "Default")
      (node (ref "Q23") (pin "2") (pinfunction "D_2") (pintype "unspecified"))
      (node (ref "R11") (pin "2") (pinfunction "2_2") (pintype "unspecified"))
      (node (ref "U13") (pin "1") (pinfunction "1_1") (pintype "unspecified"))
    )
    (net (code "48") (name "Net-(Q23-G)") (class "Default")
      (node (ref "Q23") (pin "1") (pinfunction "G_1") (pintype "unspecified"))
      (node (ref "U1") (pin "11") (pinfunction "Y10_11") (pintype "unspecified"))
    )
    (net (code "49") (name "Net-(Q24-D)") (class "Default")
      (node (ref "Q24") (pin "2") (pinfunction "D_2") (pintype "unspecified"))
      (node (ref "R10") (pin "2") (pinfunction "2_2") (pintype "unspecified"))
      (node (ref "U14") (pin "1") (pinfunction "1_1") (pintype "unspecified"))
    )
    (net (code "50") (name "Net-(Q24-G)") (class "Default")
      (node (ref "Q24") (pin "1") (pinfunction "G_1") (pintype "unspecified"))
      (node (ref "U1") (pin "10") (pinfunction "Y9_10") (pintype "unspecified"))
    )
    (net (code "51") (name "Net-(Q25-D)") (class "Default")
      (node (ref "Q25") (pin "2") (pinfunction "D_2") (pintype "unspecified"))
      (node (ref "R9") (pin "2") (pinfunction "2_2") (pintype "unspecified"))
      (node (ref "U15") (pin "1") (pinfunction "1_1") (pintype "unspecified"))
    )
    (net (code "52") (name "Net-(Q25-G)") (class "Default")
      (node (ref "Q25") (pin "1") (pinfunction "G_1") (pintype "unspecified"))
      (node (ref "U1") (pin "9") (pinfunction "Y8_9") (pintype "unspecified"))
    )
    (net (code "53") (name "Net-(Q26-D)") (class "Default")
      (node (ref "Q26") (pin "2") (pinfunction "D_2") (pintype "unspecified"))
      (node (ref "R8") (pin "2") (pinfunction "2_2") (pintype "unspecified"))
      (node (ref "U16") (pin "1") (pinfunction "1_1") (pintype "unspecified"))
    )
    (net (code "54") (name "Net-(Q26-G)") (class "Default")
      (node (ref "Q26") (pin "1") (pinfunction "G_1") (pintype "unspecified"))
      (node (ref "U1") (pin "8") (pinfunction "Y7_8") (pintype "unspecified"))
    )
    (net (code "55") (name "Net-(Q27-D)") (class "Default")
      (node (ref "Q27") (pin "2") (pinfunction "D_2") (pintype "unspecified"))
      (node (ref "R7") (pin "2") (pinfunction "2_2") (pintype "unspecified"))
      (node (ref "U17") (pin "1") (pinfunction "1_1") (pintype "unspecified"))
    )
    (net (code "56") (name "Net-(Q27-G)") (class "Default")
      (node (ref "Q27") (pin "1") (pinfunction "G_1") (pintype "unspecified"))
      (node (ref "U1") (pin "7") (pinfunction "Y6_7") (pintype "unspecified"))
    )
    (net (code "57") (name "Net-(Q28-D)") (class "Default")
      (node (ref "Q28") (pin "2") (pinfunction "D_2") (pintype "unspecified"))
      (node (ref "R6") (pin "2") (pinfunction "2_2") (pintype "unspecified"))
      (node (ref "U18") (pin "1") (pinfunction "1_1") (pintype "unspecified"))
    )
    (net (code "58") (name "Net-(Q28-G)") (class "Default")
      (node (ref "Q28") (pin "1") (pinfunction "G_1") (pintype "unspecified"))
      (node (ref "U1") (pin "6") (pinfunction "Y5_6") (pintype "unspecified"))
    )
    (net (code "59") (name "Net-(Q29-D)") (class "Default")
      (node (ref "Q29") (pin "2") (pinfunction "D_2") (pintype "unspecified"))
      (node (ref "R5") (pin "2") (pinfunction "2_2") (pintype "unspecified"))
      (node (ref "U19") (pin "1") (pinfunction "1_1") (pintype "unspecified"))
    )
    (net (code "60") (name "Net-(Q29-G)") (class "Default")
      (node (ref "Q29") (pin "1") (pinfunction "G_1") (pintype "unspecified"))
      (node (ref "U1") (pin "5") (pinfunction "Y4_5") (pintype "unspecified"))
    )
    (net (code "61") (name "Net-(Q30-D)") (class "Default")
      (node (ref "Q30") (pin "2") (pinfunction "D_2") (pintype "unspecified"))
      (node (ref "R4") (pin "2") (pinfunction "2_2") (pintype "unspecified"))
      (node (ref "U20") (pin "1") (pinfunction "1_1") (pintype "unspecified"))
    )
    (net (code "62") (name "Net-(Q30-G)") (class "Default")
      (node (ref "Q30") (pin "1") (pinfunction "G_1") (pintype "unspecified"))
      (node (ref "U1") (pin "4") (pinfunction "Y3_4") (pintype "unspecified"))
    )
    (net (code "63") (name "Net-(Q31-D)") (class "Default")
      (node (ref "Q31") (pin "2") (pinfunction "D_2") (pintype "unspecified"))
      (node (ref "R3") (pin "2") (pinfunction "2_2") (pintype "unspecified"))
      (node (ref "U21") (pin "1") (pinfunction "1_1") (pintype "unspecified"))
    )
    (net (code "64") (name "Net-(Q31-G)") (class "Default")
      (node (ref "Q31") (pin "1") (pinfunction "G_1") (pintype "unspecified"))
      (node (ref "U1") (pin "3") (pinfunction "Y2_3") (pintype "unspecified"))
    )
    (net (code "65") (name "Net-(Q32-D)") (class "Default")
      (node (ref "Q32") (pin "2") (pinfunction "D_2") (pintype "unspecified"))
      (node (ref "R2") (pin "2") (pinfunction "2_2") (pintype "unspecified"))
      (node (ref "U22") (pin "1") (pinfunction "1_1") (pintype "unspecified"))
    )
    (net (code "66") (name "Net-(Q32-G)") (class "Default")
      (node (ref "Q32") (pin "1") (pinfunction "G_1") (pintype "unspecified"))
      (node (ref "U1") (pin "2") (pinfunction "Y1_2") (pintype "unspecified"))
    )
    (net (code "67") (name "Net-(Q33-D)") (class "Default")
      (node (ref "Q33") (pin "2") (pinfunction "D_2") (pintype "unspecified"))
      (node (ref "R1") (pin "2") (pinfunction "2_2") (pintype "unspecified"))
      (node (ref "U23") (pin "1") (pinfunction "1_1") (pintype "unspecified"))
    )
    (net (code "68") (name "Net-(Q33-G)") (class "Default")
      (node (ref "Q33") (pin "1") (pinfunction "G_1") (pintype "unspecified"))
      (node (ref "U1") (pin "1") (pinfunction "Y0_1") (pintype "unspecified"))
    )
    (net (code "69") (name "Net-(R36-Pad1)") (class "Default")
      (node (ref "R36") (pin "1") (pinfunction "1_1") (pintype "unspecified"))
      (node (ref "SW1") (pin "6") (pinfunction "6_6") (pintype "unspecified"))
    )
    (net (code "70") (name "Net-(R37-Pad1)") (class "Default")
      (node (ref "R37") (pin "1") (pinfunction "1_1") (pintype "unspecified"))
      (node (ref "SW1") (pin "5") (pinfunction "5_5") (pintype "unspecified"))
    )
    (net (code "71") (name "Net-(U1-A0)") (class "Default")
      (node (ref "U1") (pin "23") (pinfunction "A0_23") (pintype "unspecified"))
      (node (ref "U4") (pin "1") (pinfunction "QB_1") (pintype "unspecified"))
      (node (ref "U6") (pin "9") (pinfunction "A1_9") (pintype "unspecified"))
    )
    (net (code "72") (name "Net-(U1-A1)") (class "Default")
      (node (ref "U1") (pin "22") (pinfunction "A1_22") (pintype "unspecified"))
      (node (ref "U4") (pin "2") (pinfunction "QC_2") (pintype "unspecified"))
      (node (ref "U6") (pin "8") (pinfunction "A2_8") (pintype "unspecified"))
    )
    (net (code "73") (name "Net-(U1-A2)") (class "Default")
      (node (ref "U1") (pin "21") (pinfunction "A2_21") (pintype "unspecified"))
      (node (ref "U4") (pin "3") (pinfunction "QD_3") (pintype "unspecified"))
      (node (ref "U6") (pin "7") (pinfunction "A3_7") (pintype "unspecified"))
    )
    (net (code "74") (name "Net-(U1-A3)") (class "Default")
      (node (ref "U1") (pin "20") (pinfunction "A3_20") (pintype "unspecified"))
      (node (ref "U4") (pin "4") (pinfunction "QE_4") (pintype "unspecified"))
      (node (ref "U6") (pin "6") (pinfunction "A4_6") (pintype "unspecified"))
    )
    (net (code "75") (name "Net-(U2-MR)") (class "Default")
      (node (ref "R17") (pin "2") (pinfunction "2_2") (pintype "unspecified"))
      (node (ref "U2") (pin "12") (pinfunction "MR_12") (pintype "unspecified"))
    )
    (net (code "76") (name "Net-(U2-Q4)") (class "Default")
      (node (ref "J1") (pin "1") (pinfunction "1_1") (pintype "unspecified"))
      (node (ref "U2") (pin "7") (pinfunction "Q4_7") (pintype "unspecified"))
    )
    (net (code "77") (name "Net-(U2-Q5)") (class "Default")
      (node (ref "J1") (pin "2") (pinfunction "2_2") (pintype "unspecified"))
      (node (ref "U2") (pin "5") (pinfunction "Q5_5") (pintype "unspecified"))
    )
    (net (code "78") (name "Net-(U2-Q6)") (class "Default")
      (node (ref "J1") (pin "3") (pinfunction "3_3") (pintype "unspecified"))
      (node (ref "U2") (pin "4") (pinfunction "Q6_4") (pintype "unspecified"))
    )
    (net (code "79") (name "Net-(U2-Q7)") (class "Default")
      (node (ref "J1") (pin "4") (pinfunction "4_4") (pintype "unspecified"))
      (node (ref "U2") (pin "6") (pinfunction "Q7_6") (pintype "unspecified"))
    )
    (net (code "80") (name "Net-(U2-Q8)") (class "Default")
      (node (ref "J1") (pin "5") (pinfunction "5_5") (pintype "unspecified"))
      (node (ref "U2") (pin "14") (pinfunction "Q8_14") (pintype "unspecified"))
    )
    (net (code "81") (name "Net-(U2-Q9)") (class "Default")
      (node (ref "J1") (pin "6") (pinfunction "6_6") (pintype "unspecified"))
      (node (ref "U2") (pin "13") (pinfunction "Q9_13") (pintype "unspecified"))
    )
    (net (code "82") (name "Net-(U2-Q10)") (class "Default")
      (node (ref "J1") (pin "7") (pinfunction "7_7") (pintype "unspecified"))
      (node (ref "U2") (pin "15") (pinfunction "Q10_15") (pintype "unspecified"))
    )
    (net (code "83") (name "Net-(U2-Q12)") (class "Default")
      (node (ref "J1") (pin "8") (pinfunction "8_8") (pintype "unspecified"))
      (node (ref "U2") (pin "1") (pinfunction "Q12_1") (pintype "unspecified"))
    )
    (net (code "84") (name "Net-(U2-Q13)") (class "Default")
      (node (ref "J1") (pin "9") (pinfunction "9_9") (pintype "unspecified"))
      (node (ref "U2") (pin "2") (pinfunction "Q13_2") (pintype "unspecified"))
    )
    (net (code "85") (name "Net-(U2-Q14)") (class "Default")
      (node (ref "J1") (pin "10") (pinfunction "10_10") (pintype "unspecified"))
      (node (ref "U2") (pin "3") (pinfunction "Q14_3") (pintype "unspecified"))
    )
    (net (code "86") (name "Net-(U2-φI)") (class "Default")
      (node (ref "C3") (pin "2") (pinfunction "2_2") (pintype "unspecified"))
      (node (ref "R21") (pin "1") (pinfunction "1_1") (pintype "unspecified"))
      (node (ref "U2") (pin "11") (pinfunction "φI_11") (pintype "unspecified"))
      (node (ref "U4") (pin "11") (pinfunction "CCLK_11") (pintype "unspecified"))
      (node (ref "U4") (pin "13") (pinfunction "RCLK_13") (pintype "unspecified"))
      (node (ref "X1") (pin "1") (pinfunction "1_1") (pintype "unspecified"))
    )
    (net (code "87") (name "Net-(U2-φO#)") (class "Default")
      (node (ref "R21") (pin "2") (pinfunction "2_2") (pintype "unspecified"))
      (node (ref "R22") (pin "2") (pinfunction "2_2") (pintype "unspecified"))
      (node (ref "U2") (pin "10") (pinfunction "φO#_10") (pintype "unspecified"))
    )
    (net (code "88") (name "Net-(U3-A0)") (class "Default")
      (node (ref "U3") (pin "2") (pinfunction "A0_2") (pintype "unspecified"))
      (node (ref "U5") (pin "2") (pinfunction "A0_2") (pintype "unspecified"))
      (node (ref "U6") (pin "11") (pinfunction "I/O0_11") (pintype "unspecified"))
    )
    (net (code "89") (name "Net-(U3-A1)") (class "Default")
      (node (ref "U3") (pin "3") (pinfunction "A1_3") (pintype "unspecified"))
      (node (ref "U5") (pin "3") (pinfunction "A1_3") (pintype "unspecified"))
      (node (ref "U6") (pin "12") (pinfunction "I/O1_12") (pintype "unspecified"))
    )
    (net (code "90") (name "Net-(U3-A2)") (class "Default")
      (node (ref "U3") (pin "4") (pinfunction "A2_4") (pintype "unspecified"))
      (node (ref "U5") (pin "4") (pinfunction "A2_4") (pintype "unspecified"))
      (node (ref "U6") (pin "13") (pinfunction "I/O2_13") (pintype "unspecified"))
    )
    (net (code "91") (name "Net-(U3-A4)") (class "Default")
      (node (ref "U3") (pin "6") (pinfunction "A4_6") (pintype "unspecified"))
      (node (ref "U5") (pin "6") (pinfunction "A4_6") (pintype "unspecified"))
      (node (ref "U6") (pin "16") (pinfunction "I/O4_16") (pintype "unspecified"))
    )
    (net (code "92") (name "Net-(U3-A5)") (class "Default")
      (node (ref "U3") (pin "7") (pinfunction "A5_7") (pintype "unspecified"))
      (node (ref "U5") (pin "7") (pinfunction "A5_7") (pintype "unspecified"))
      (node (ref "U6") (pin "17") (pinfunction "I/O5_17") (pintype "unspecified"))
    )
    (net (code "93") (name "Net-(U3-A6)") (class "Default")
      (node (ref "U3") (pin "8") (pinfunction "A6_8") (pintype "unspecified"))
      (node (ref "U5") (pin "8") (pinfunction "A6_8") (pintype "unspecified"))
      (node (ref "U6") (pin "18") (pinfunction "I/O6_18") (pintype "unspecified"))
    )
    (net (code "94") (name "Net-(U3-A7)") (class "Default")
      (node (ref "U3") (pin "9") (pinfunction "A7_9") (pintype "unspecified"))
      (node (ref "U5") (pin "9") (pinfunction "A7_9") (pintype "unspecified"))
      (node (ref "U6") (pin "19") (pinfunction "I/O7_19") (pintype "unspecified"))
    )
    (net (code "95") (name "Net-(U4-CCKEN#)") (class "Default")
      (node (ref "R19") (pin "2") (pinfunction "2_2") (pintype "unspecified"))
      (node (ref "U4") (pin "12") (pinfunction "CCKEN#_12") (pintype "unspecified"))
      (node (ref "U4") (pin "14") (pinfunction "OE#_14") (pintype "unspecified"))
    )
    (net (code "96") (name "Net-(U4-CCLR#)") (class "Default")
      (node (ref "R20") (pin "1") (pinfunction "1_1") (pintype "unspecified"))
      (node (ref "U4") (pin "10") (pinfunction "CCLR#_10") (pintype "unspecified"))
    )
    (net (code "97") (name "Net-(U4-QF)") (class "Default")
      (node (ref "J2") (pin "3") (pinfunction "3_3") (pintype "input"))
      (node (ref "U4") (pin "5") (pinfunction "QF_5") (pintype "unspecified"))
    )
    (net (code "98") (name "Net-(U4-QG)") (class "Default")
      (node (ref "J2") (pin "2") (pinfunction "2_2") (pintype "input"))
      (node (ref "U4") (pin "6") (pinfunction "QG_6") (pintype "unspecified"))
    )
    (net (code "99") (name "Net-(U4-QH)") (class "Default")
      (node (ref "J2") (pin "1") (pinfunction "1_1") (pintype "input"))
      (node (ref "U4") (pin "7") (pinfunction "QH_7") (pintype "unspecified"))
    )
    (net (code "100") (name "Net-(U6-A5)") (class "Default")
      (node (ref "R35") (pin "1") (pinfunction "1_1") (pintype "unspecified"))
      (node (ref "SW1") (pin "7") (pinfunction "7_7") (pintype "unspecified"))
      (node (ref "U6") (pin "5") (pinfunction "A5_5") (pintype "unspecified"))
    )
    (net (code "101") (name "Net-(U6-A6)") (class "Default")
      (node (ref "R34") (pin "1") (pinfunction "1_1") (pintype "unspecified"))
      (node (ref "SW1") (pin "8") (pinfunction "8_8") (pintype "unspecified"))
      (node (ref "U6") (pin "4") (pinfunction "A6_4") (pintype "unspecified"))
    )
    (net (code "102") (name "Net-(U6-A7)") (class "Default")
      (node (ref "DIP1") (pin "9") (pinfunction "9_9") (pintype "unspecified"))
      (node (ref "R33") (pin "1") (pinfunction "1_1") (pintype "unspecified"))
      (node (ref "U6") (pin "3") (pinfunction "A7_3") (pintype "unspecified"))
    )
    (net (code "103") (name "Net-(U6-A8)") (class "Default")
      (node (ref "DIP1") (pin "10") (pinfunction "10_10") (pintype "unspecified"))
      (node (ref "R32") (pin "1") (pinfunction "1_1") (pintype "unspecified"))
      (node (ref "U6") (pin "25") (pinfunction "A8_25") (pintype "unspecified"))
    )
    (net (code "104") (name "Net-(U6-A9)") (class "Default")
      (node (ref "DIP1") (pin "11") (pinfunction "11_11") (pintype "unspecified"))
      (node (ref "R31") (pin "1") (pinfunction "1_1") (pintype "unspecified"))
      (node (ref "U6") (pin "24") (pinfunction "A9_24") (pintype "unspecified"))
    )
    (net (code "105") (name "Net-(U6-A10)") (class "Default")
      (node (ref "DIP1") (pin "12") (pinfunction "12_12") (pintype "unspecified"))
      (node (ref "R30") (pin "1") (pinfunction "1_1") (pintype "unspecified"))
      (node (ref "U6") (pin "21") (pinfunction "A10_21") (pintype "unspecified"))
    )
    (net (code "106") (name "Net-(U6-A11)") (class "Default")
      (node (ref "DIP1") (pin "13") (pinfunction "13_13") (pintype "unspecified"))
      (node (ref "R29") (pin "1") (pinfunction "1_1") (pintype "unspecified"))
      (node (ref "U6") (pin "23") (pinfunction "A11_23") (pintype "unspecified"))
    )
    (net (code "107") (name "Net-(U6-A12)") (class "Default")
      (node (ref "DIP1") (pin "14") (pinfunction "14_14") (pintype "unspecified"))
      (node (ref "R28") (pin "1") (pinfunction "1_1") (pintype "unspecified"))
      (node (ref "U6") (pin "2") (pinfunction "A12_2") (pintype "unspecified"))
    )
    (net (code "108") (name "Net-(U6-A13)") (class "Default")
      (node (ref "DIP1") (pin "15") (pinfunction "15_15") (pintype "unspecified"))
      (node (ref "R27") (pin "1") (pinfunction "1_1") (pintype "unspecified"))
      (node (ref "U6") (pin "26") (pinfunction "A13_26") (pintype "unspecified"))
    )
    (net (code "109") (name "Net-(U6-A14)") (class "Default")
      (node (ref "DIP1") (pin "16") (pinfunction "16_16") (pintype "unspecified"))
      (node (ref "R26") (pin "1") (pinfunction "1_1") (pintype "unspecified"))
      (node (ref "U6") (pin "1") (pinfunction "A14_1") (pintype "unspecified"))
    )
    (net (code "110") (name "Net-(U6-CE#)") (class "Default")
      (node (ref "R25") (pin "1") (pinfunction "1_1") (pintype "unspecified"))
      (node (ref "U6") (pin "20") (pinfunction "CE#_20") (pintype "unspecified"))
    )
    (net (code "111") (name "Net-(U6-OE#)") (class "Default")
      (node (ref "R24") (pin "1") (pinfunction "1_1") (pintype "unspecified"))
      (node (ref "U6") (pin "22") (pinfunction "OE#_22") (pintype "unspecified"))
    )
    (net (code "112") (name "Net-(U6-WE#)") (class "Default")
      (node (ref "R23") (pin "1") (pinfunction "1_1") (pintype "unspecified"))
      (node (ref "U6") (pin "27") (pinfunction "WE#_27") (pintype "unspecified"))
    )
    (net (code "113") (name "O") (class "Default")
      (node (ref "LED111") (pin "1") (pinfunction "K_1") (pintype "unspecified"))
      (node (ref "LED127") (pin "1") (pinfunction "K_1") (pintype "unspecified"))
      (node (ref "LED143") (pin "1") (pinfunction "K_1") (pintype "unspecified"))
      (node (ref "LED15") (pin "1") (pinfunction "K_1") (pintype "unspecified"))
      (node (ref "LED159") (pin "1") (pinfunction "K_1") (pintype "unspecified"))
      (node (ref "LED175") (pin "1") (pinfunction "K_1") (pintype "unspecified"))
      (node (ref "LED191") (pin "1") (pinfunction "K_1") (pintype "unspecified"))
      (node (ref "LED207") (pin "1") (pinfunction "K_1") (pintype "unspecified"))
      (node (ref "LED223") (pin "1") (pinfunction "K_1") (pintype "unspecified"))
      (node (ref "LED239") (pin "1") (pinfunction "K_1") (pintype "unspecified"))
      (node (ref "LED255") (pin "1") (pinfunction "K_1") (pintype "unspecified"))
      (node (ref "LED31") (pin "1") (pinfunction "K_1") (pintype "unspecified"))
      (node (ref "LED47") (pin "1") (pinfunction "K_1") (pintype "unspecified"))
      (node (ref "LED63") (pin "1") (pinfunction "K_1") (pintype "unspecified"))
      (node (ref "LED79") (pin "1") (pinfunction "K_1") (pintype "unspecified"))
      (node (ref "LED95") (pin "1") (pinfunction "K_1") (pintype "unspecified"))
      (node (ref "U9") (pin "2") (pinfunction "2_2") (pintype "unspecified"))
    )
    (net (code "114") (name "P") (class "Default")
      (node (ref "LED112") (pin "1") (pinfunction "K_1") (pintype "unspecified"))
      (node (ref "LED128") (pin "1") (pinfunction "K_1") (pintype "unspecified"))
      (node (ref "LED144") (pin "1") (pinfunction "K_1") (pintype "unspecified"))
      (node (ref "LED16") (pin "1") (pinfunction "K_1") (pintype "unspecified"))
      (node (ref "LED160") (pin "1") (pinfunction "K_1") (pintype "unspecified"))
      (node (ref "LED176") (pin "1") (pinfunction "K_1") (pintype "unspecified"))
      (node (ref "LED192") (pin "1") (pinfunction "K_1") (pintype "unspecified"))
      (node (ref "LED208") (pin "1") (pinfunction "K_1") (pintype "unspecified"))
      (node (ref "LED224") (pin "1") (pinfunction "K_1") (pintype "unspecified"))
      (node (ref "LED240") (pin "1") (pinfunction "K_1") (pintype "unspecified"))
      (node (ref "LED256") (pin "1") (pinfunction "K_1") (pintype "unspecified"))
      (node (ref "LED32") (pin "1") (pinfunction "K_1") (pintype "unspecified"))
      (node (ref "LED48") (pin "1") (pinfunction "K_1") (pintype "unspecified"))
      (node (ref "LED64") (pin "1") (pinfunction "K_1") (pintype "unspecified"))
      (node (ref "LED80") (pin "1") (pinfunction "K_1") (pintype "unspecified"))
      (node (ref "LED96") (pin "1") (pinfunction "K_1") (pintype "unspecified"))
      (node (ref "U8") (pin "2") (pinfunction "2_2") (pintype "unspecified"))
    )
    (net (code "115") (name "unconnected-(U2-φO-Pad9)") (class "Default")
      (node (ref "U2") (pin "9") (pinfunction "φO_9") (pintype "unspecified+no_connect"))
    )
    (net (code "116") (name "unconnected-(U4-RCO#-Pad9)") (class "Default")
      (node (ref "U4") (pin "9") (pinfunction "RCO#_9") (pintype "unspecified+no_connect"))
    )
  )
)
